# Eight_bit_v1.net
KiCad netlist of a schematic drawn in Altium Designer
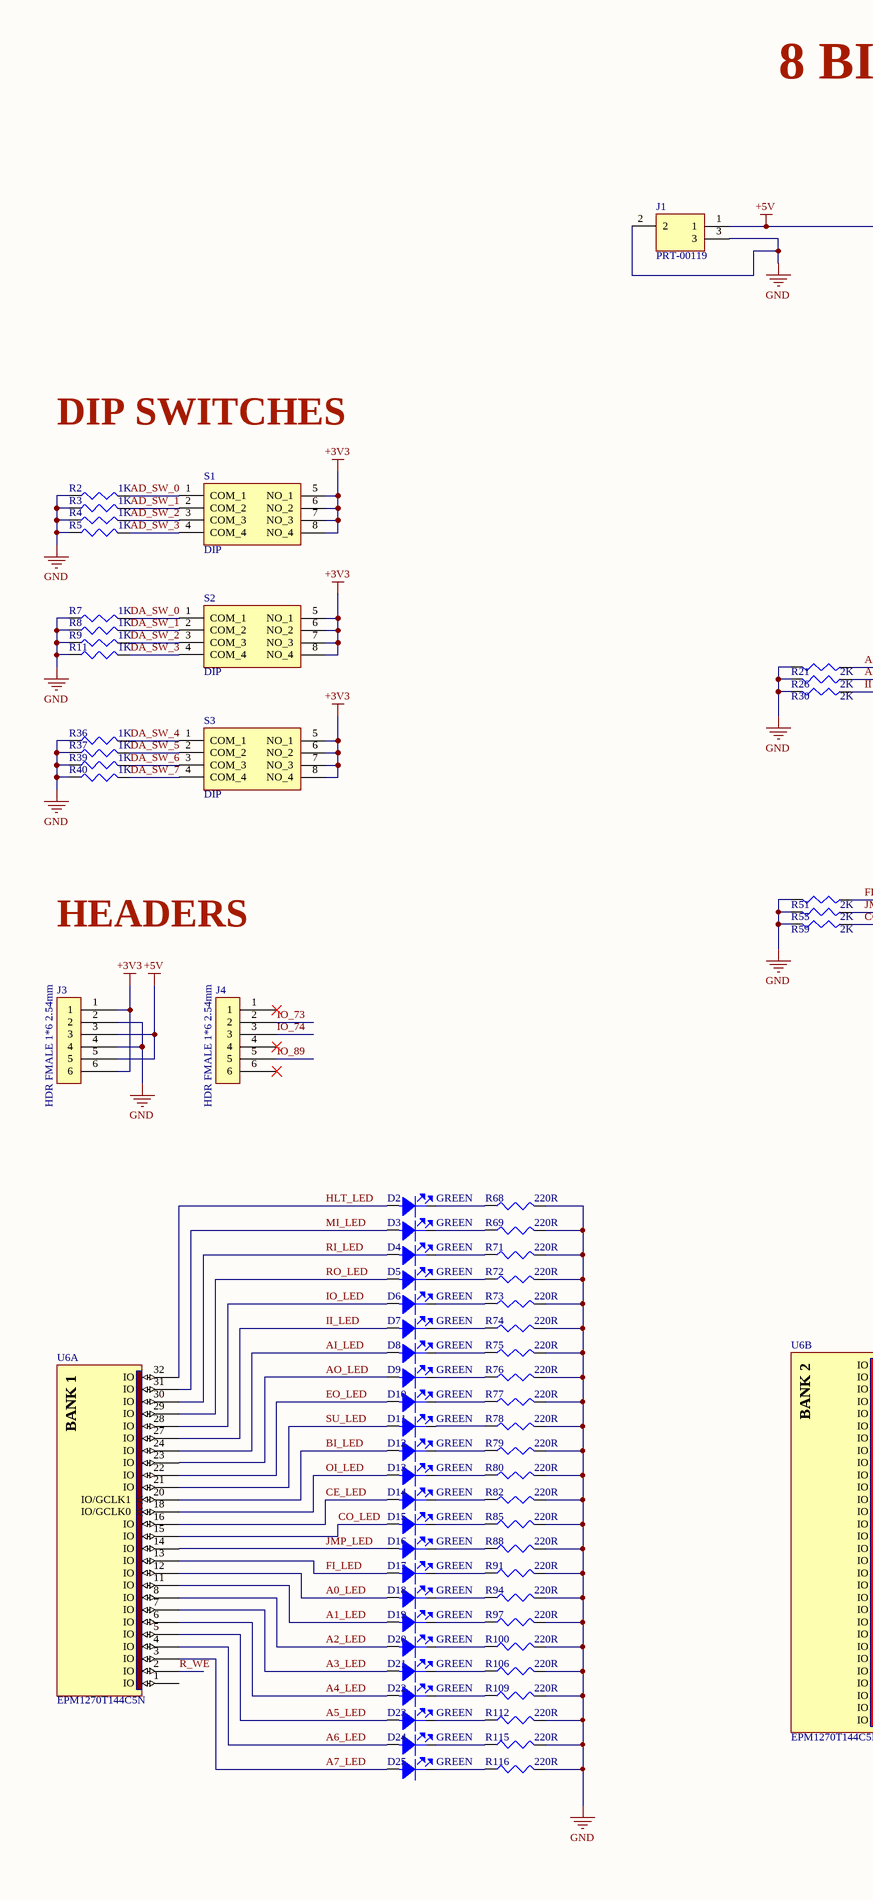
[diagram p0: Eight_bit_v1.SchDoc, left]
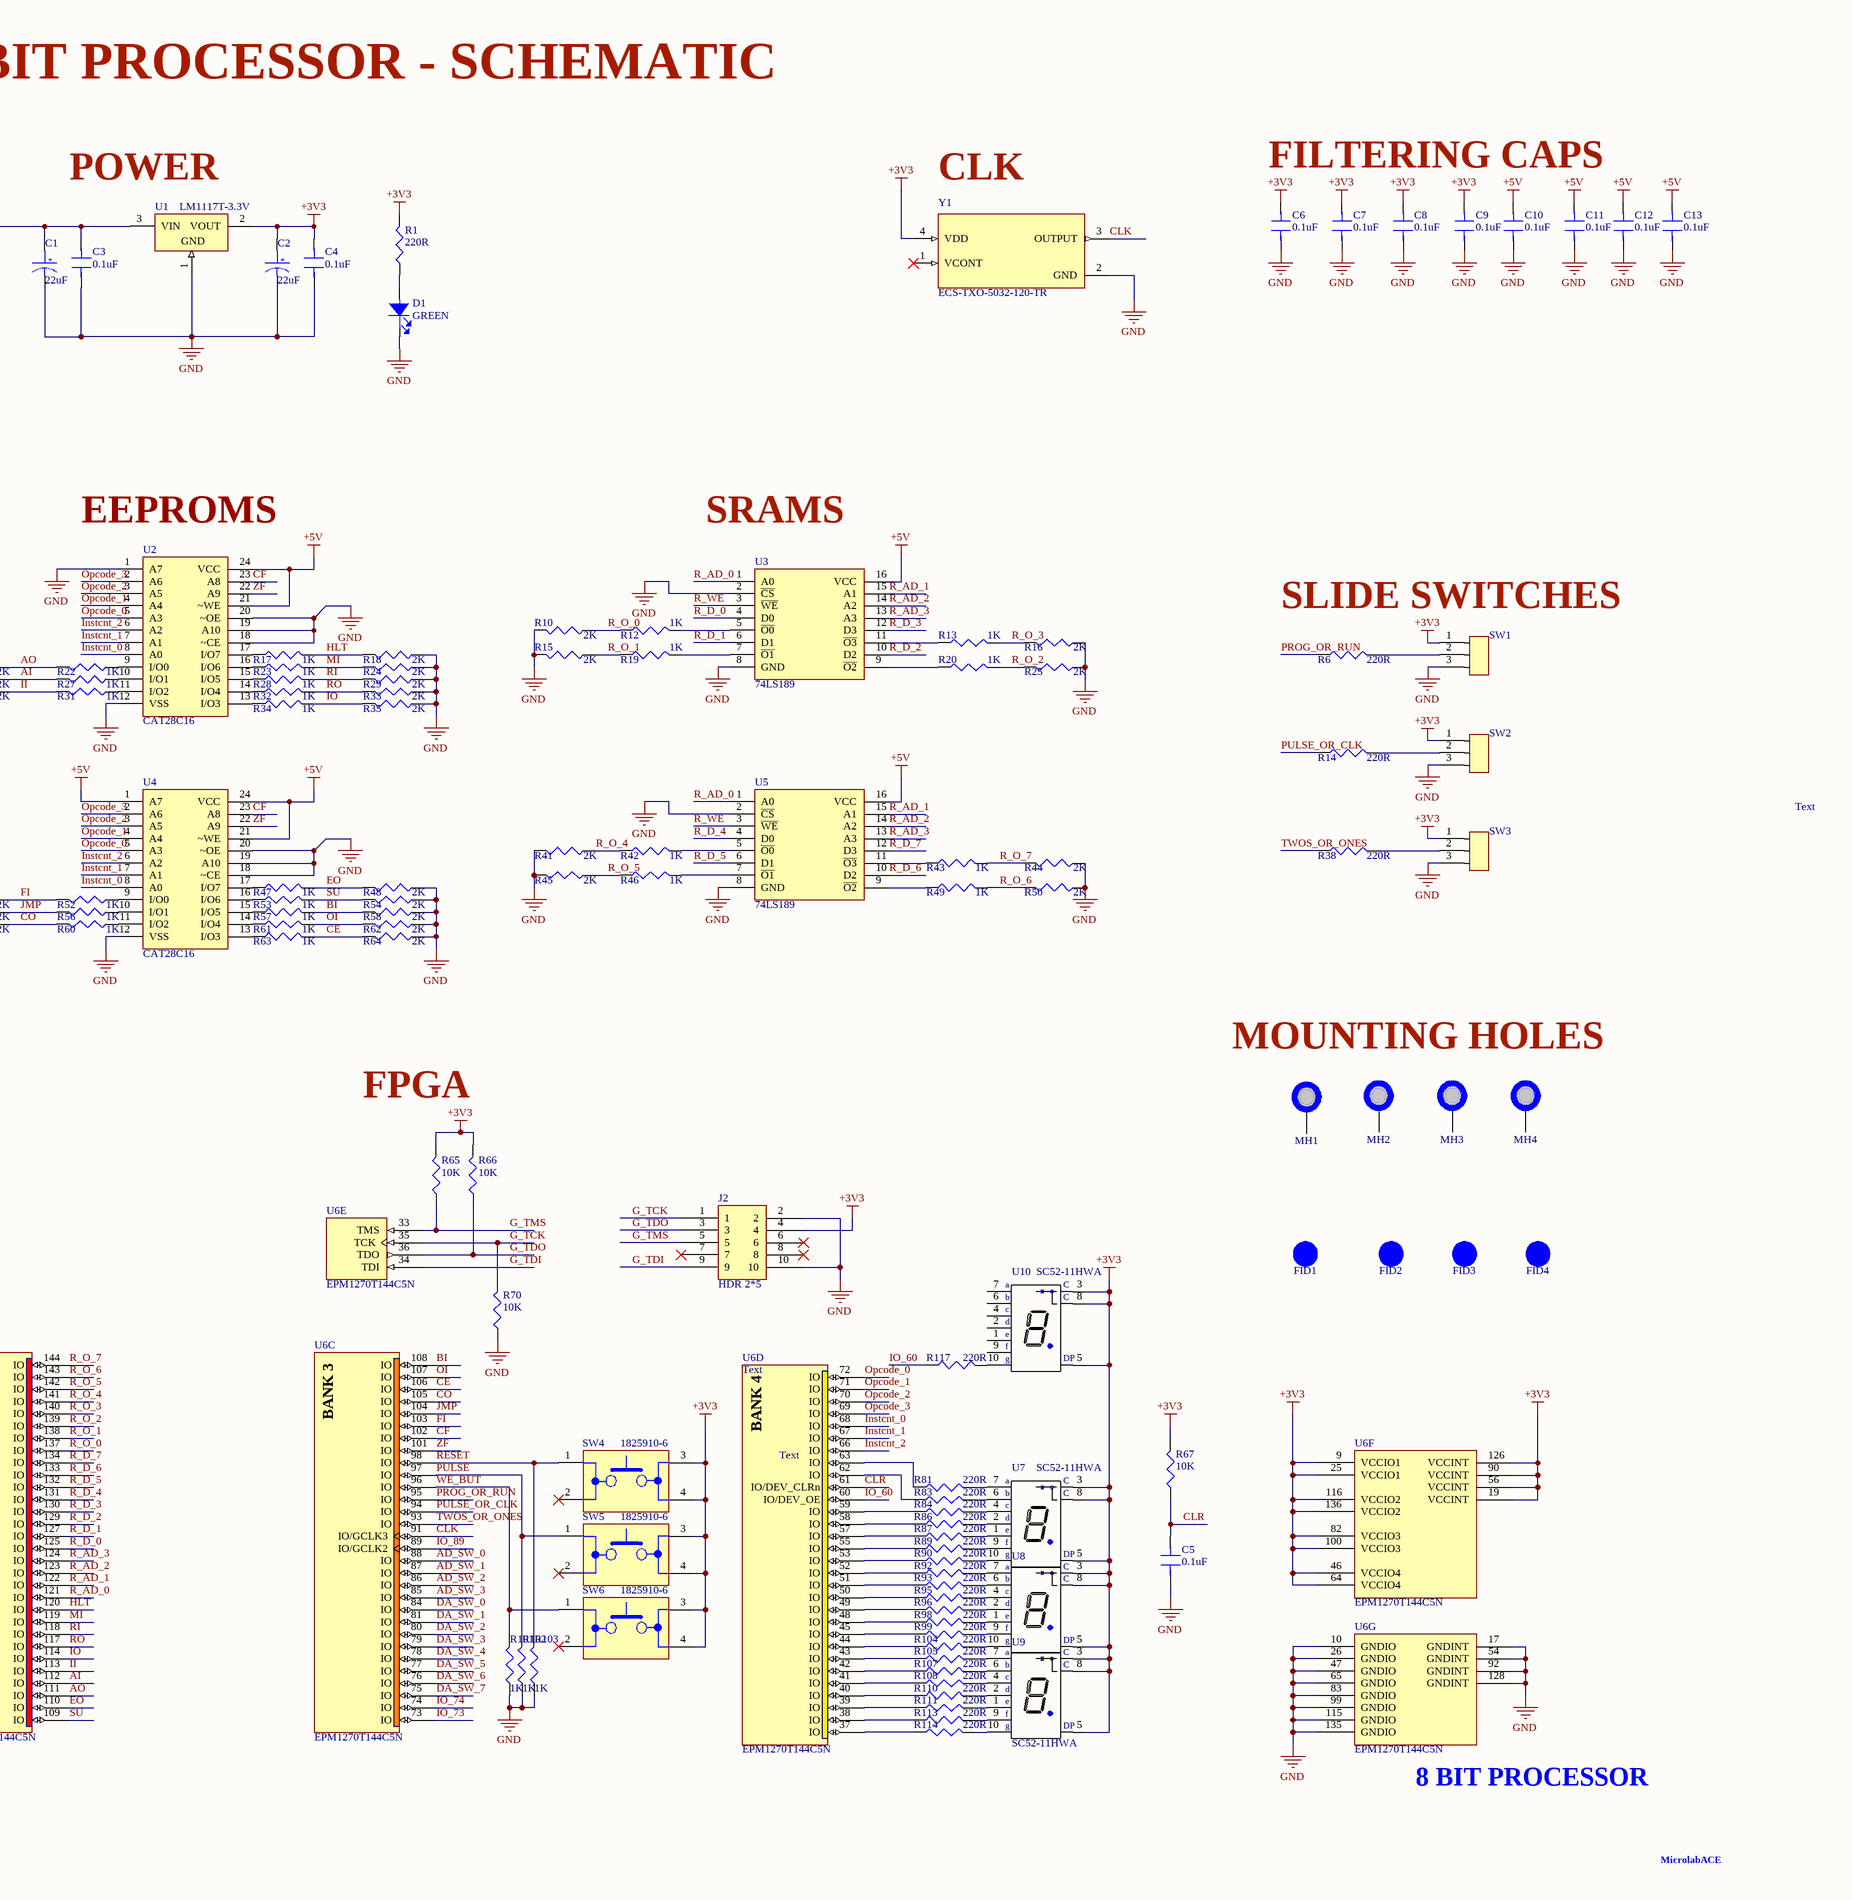
[diagram p1: Eight_bit_v1.SchDoc, right]

(export (version "E")
  (design (tool "Eeschema 10.0.6"))
  (components
    (comp (ref "C1")
      (value "22uF")
      (footprint "CAPPRD200W50D550H1250")
      (description "Cap Aluminum 22uF 25V 20% Radial 2000 hr 85C Ammo Pack")
      (fields
        (field (name "MANUFACTURER") "Panasonic")
        (field (name "MANUFACTURER PART NUMBER") "ECA-1EM220I")
      )
      (libsource (lib "Eight_bit_v1") (part "ECA-1EM220I"))
    )
    (comp (ref "C2")
      (value "22uF")
      (footprint "CAPPRD200W50D550H1250")
      (description "Cap Aluminum 22uF 25V 20% Radial 2000 hr 85C Ammo Pack")
      (fields
        (field (name "MANUFACTURER") "Panasonic")
        (field (name "MANUFACTURER PART NUMBER") "ECA-1EM220I")
      )
      (libsource (lib "Eight_bit_v1") (part "ECA-1EM220I"))
    )
    (comp (ref "C3")
      (value "0.1uF")
      (footprint "C0805")
      (description "Cap Ceramic 0.1uF 50V X7R 10% SMD 2.0 x 1.2 mm 125 C Paper T/R")
      (fields
        (field (name "MANUFACTURER") "KEMET")
        (field (name "MANUFACTURER PART NUMBER") "C0805C104K5RACTU")
      )
      (libsource (lib "Eight_bit_v1") (part "C0805C104K5RACTU"))
    )
    (comp (ref "C4")
      (value "0.1uF")
      (footprint "C0805")
      (description "Cap Ceramic 0.1uF 50V X7R 10% SMD 2.0 x 1.2 mm 125 C Paper T/R")
      (fields
        (field (name "MANUFACTURER") "KEMET")
        (field (name "MANUFACTURER PART NUMBER") "C0805C104K5RACTU")
      )
      (libsource (lib "Eight_bit_v1") (part "C0805C104K5RACTU"))
    )
    (comp (ref "C5")
      (value "0.1uF")
      (footprint "C0805")
      (description "Cap Ceramic 0.1uF 50V X7R 10% SMD 2.0 x 1.2 mm 125 C Paper T/R")
      (fields
        (field (name "MANUFACTURER") "KEMET")
        (field (name "MANUFACTURER PART NUMBER") "C0805C104K5RACTU")
      )
      (libsource (lib "Eight_bit_v1") (part "C0805C104K5RACTU"))
    )
    (comp (ref "C6")
      (value "0.1uF")
      (footprint "C0805")
      (description "Cap Ceramic 0.1uF 50V X7R 10% SMD 2.0 x 1.2 mm 125 C Paper T/R")
      (fields
        (field (name "MANUFACTURER") "KEMET")
        (field (name "MANUFACTURER PART NUMBER") "C0805C104K5RACTU")
      )
      (libsource (lib "Eight_bit_v1") (part "C0805C104K5RACTU"))
    )
    (comp (ref "C7")
      (value "0.1uF")
      (footprint "C0805")
      (description "Cap Ceramic 0.1uF 50V X7R 10% SMD 2.0 x 1.2 mm 125 C Paper T/R")
      (fields
        (field (name "MANUFACTURER") "KEMET")
        (field (name "MANUFACTURER PART NUMBER") "C0805C104K5RACTU")
      )
      (libsource (lib "Eight_bit_v1") (part "C0805C104K5RACTU"))
    )
    (comp (ref "C8")
      (value "0.1uF")
      (footprint "C0805")
      (description "Cap Ceramic 0.1uF 50V X7R 10% SMD 2.0 x 1.2 mm 125 C Paper T/R")
      (fields
        (field (name "MANUFACTURER") "KEMET")
        (field (name "MANUFACTURER PART NUMBER") "C0805C104K5RACTU")
      )
      (libsource (lib "Eight_bit_v1") (part "C0805C104K5RACTU"))
    )
    (comp (ref "C9")
      (value "0.1uF")
      (footprint "C0805")
      (description "Cap Ceramic 0.1uF 50V X7R 10% SMD 2.0 x 1.2 mm 125 C Paper T/R")
      (fields
        (field (name "MANUFACTURER") "KEMET")
        (field (name "MANUFACTURER PART NUMBER") "C0805C104K5RACTU")
      )
      (libsource (lib "Eight_bit_v1") (part "C0805C104K5RACTU"))
    )
    (comp (ref "C10")
      (value "0.1uF")
      (footprint "C0805")
      (description "Cap Ceramic 0.1uF 50V X7R 10% SMD 2.0 x 1.2 mm 125 C Paper T/R")
      (fields
        (field (name "MANUFACTURER") "KEMET")
        (field (name "MANUFACTURER PART NUMBER") "C0805C104K5RACTU")
      )
      (libsource (lib "Eight_bit_v1") (part "C0805C104K5RACTU"))
    )
    (comp (ref "C11")
      (value "0.1uF")
      (footprint "C0805")
      (description "Cap Ceramic 0.1uF 50V X7R 10% SMD 2.0 x 1.2 mm 125 C Paper T/R")
      (fields
        (field (name "MANUFACTURER") "KEMET")
        (field (name "MANUFACTURER PART NUMBER") "C0805C104K5RACTU")
      )
      (libsource (lib "Eight_bit_v1") (part "C0805C104K5RACTU"))
    )
    (comp (ref "C12")
      (value "0.1uF")
      (footprint "C0805")
      (description "Cap Ceramic 0.1uF 50V X7R 10% SMD 2.0 x 1.2 mm 125 C Paper T/R")
      (fields
        (field (name "MANUFACTURER") "KEMET")
        (field (name "MANUFACTURER PART NUMBER") "C0805C104K5RACTU")
      )
      (libsource (lib "Eight_bit_v1") (part "C0805C104K5RACTU"))
    )
    (comp (ref "C13")
      (value "0.1uF")
      (footprint "C0805")
      (description "Cap Ceramic 0.1uF 50V X7R 10% SMD 2.0 x 1.2 mm 125 C Paper T/R")
      (fields
        (field (name "MANUFACTURER") "KEMET")
        (field (name "MANUFACTURER PART NUMBER") "C0805C104K5RACTU")
      )
      (libsource (lib "Eight_bit_v1") (part "C0805C104K5RACTU"))
    )
    (comp (ref "D1")
      (value "GREEN")
      (footprint "LED_0805")
      (description "LED Uni-Color Green 572nm 2-Pin SMD T/R")
      (fields
        (field (name "MANUFACTURER") "Osram Opto")
        (field (name "MANUFACTURER PART NUMBER") "LGR971-KN-1")
      )
      (libsource (lib "Eight_bit_v1") (part "LGR971-KN-1"))
    )
    (comp (ref "D2")
      (value "GREEN")
      (footprint "LED_0805")
      (description "LED Uni-Color Green 572nm 2-Pin SMD T/R")
      (fields
        (field (name "MANUFACTURER") "Osram Opto")
        (field (name "MANUFACTURER PART NUMBER") "LGR971-KN-1")
      )
      (libsource (lib "Eight_bit_v1") (part "LGR971-KN-1"))
    )
    (comp (ref "D3")
      (value "GREEN")
      (footprint "LED_0805")
      (description "LED Uni-Color Green 572nm 2-Pin SMD T/R")
      (fields
        (field (name "MANUFACTURER") "Osram Opto")
        (field (name "MANUFACTURER PART NUMBER") "LGR971-KN-1")
      )
      (libsource (lib "Eight_bit_v1") (part "LGR971-KN-1"))
    )
    (comp (ref "D4")
      (value "GREEN")
      (footprint "LED_0805")
      (description "LED Uni-Color Green 572nm 2-Pin SMD T/R")
      (fields
        (field (name "MANUFACTURER") "Osram Opto")
        (field (name "MANUFACTURER PART NUMBER") "LGR971-KN-1")
      )
      (libsource (lib "Eight_bit_v1") (part "LGR971-KN-1"))
    )
    (comp (ref "D5")
      (value "GREEN")
      (footprint "LED_0805")
      (description "LED Uni-Color Green 572nm 2-Pin SMD T/R")
      (fields
        (field (name "MANUFACTURER") "Osram Opto")
        (field (name "MANUFACTURER PART NUMBER") "LGR971-KN-1")
      )
      (libsource (lib "Eight_bit_v1") (part "LGR971-KN-1"))
    )
    (comp (ref "D6")
      (value "GREEN")
      (footprint "LED_0805")
      (description "LED Uni-Color Green 572nm 2-Pin SMD T/R")
      (fields
        (field (name "MANUFACTURER") "Osram Opto")
        (field (name "MANUFACTURER PART NUMBER") "LGR971-KN-1")
      )
      (libsource (lib "Eight_bit_v1") (part "LGR971-KN-1"))
    )
    (comp (ref "D7")
      (value "GREEN")
      (footprint "LED_0805")
      (description "LED Uni-Color Green 572nm 2-Pin SMD T/R")
      (fields
        (field (name "MANUFACTURER") "Osram Opto")
        (field (name "MANUFACTURER PART NUMBER") "LGR971-KN-1")
      )
      (libsource (lib "Eight_bit_v1") (part "LGR971-KN-1"))
    )
    (comp (ref "D8")
      (value "GREEN")
      (footprint "LED_0805")
      (description "LED Uni-Color Green 572nm 2-Pin SMD T/R")
      (fields
        (field (name "MANUFACTURER") "Osram Opto")
        (field (name "MANUFACTURER PART NUMBER") "LGR971-KN-1")
      )
      (libsource (lib "Eight_bit_v1") (part "LGR971-KN-1"))
    )
    (comp (ref "D9")
      (value "GREEN")
      (footprint "LED_0805")
      (description "LED Uni-Color Green 572nm 2-Pin SMD T/R")
      (fields
        (field (name "MANUFACTURER") "Osram Opto")
        (field (name "MANUFACTURER PART NUMBER") "LGR971-KN-1")
      )
      (libsource (lib "Eight_bit_v1") (part "LGR971-KN-1"))
    )
    (comp (ref "D10")
      (value "GREEN")
      (footprint "LED_0805")
      (description "LED Uni-Color Green 572nm 2-Pin SMD T/R")
      (fields
        (field (name "MANUFACTURER") "Osram Opto")
        (field (name "MANUFACTURER PART NUMBER") "LGR971-KN-1")
      )
      (libsource (lib "Eight_bit_v1") (part "LGR971-KN-1"))
    )
    (comp (ref "D11")
      (value "GREEN")
      (footprint "LED_0805")
      (description "LED Uni-Color Green 572nm 2-Pin SMD T/R")
      (fields
        (field (name "MANUFACTURER") "Osram Opto")
        (field (name "MANUFACTURER PART NUMBER") "LGR971-KN-1")
      )
      (libsource (lib "Eight_bit_v1") (part "LGR971-KN-1"))
    )
    (comp (ref "D12")
      (value "GREEN")
      (footprint "LED_0805")
      (description "LED Uni-Color Green 572nm 2-Pin SMD T/R")
      (fields
        (field (name "MANUFACTURER") "Osram Opto")
        (field (name "MANUFACTURER PART NUMBER") "LGR971-KN-1")
      )
      (libsource (lib "Eight_bit_v1") (part "LGR971-KN-1"))
    )
    (comp (ref "D13")
      (value "GREEN")
      (footprint "LED_0805")
      (description "LED Uni-Color Green 572nm 2-Pin SMD T/R")
      (fields
        (field (name "MANUFACTURER") "Osram Opto")
        (field (name "MANUFACTURER PART NUMBER") "LGR971-KN-1")
      )
      (libsource (lib "Eight_bit_v1") (part "LGR971-KN-1"))
    )
    (comp (ref "D14")
      (value "GREEN")
      (footprint "LED_0805")
      (description "LED Uni-Color Green 572nm 2-Pin SMD T/R")
      (fields
        (field (name "MANUFACTURER") "Osram Opto")
        (field (name "MANUFACTURER PART NUMBER") "LGR971-KN-1")
      )
      (libsource (lib "Eight_bit_v1") (part "LGR971-KN-1"))
    )
    (comp (ref "D15")
      (value "GREEN")
      (footprint "LED_0805")
      (description "LED Uni-Color Green 572nm 2-Pin SMD T/R")
      (fields
        (field (name "MANUFACTURER") "Osram Opto")
        (field (name "MANUFACTURER PART NUMBER") "LGR971-KN-1")
      )
      (libsource (lib "Eight_bit_v1") (part "LGR971-KN-1"))
    )
    (comp (ref "D16")
      (value "GREEN")
      (footprint "LED_0805")
      (description "LED Uni-Color Green 572nm 2-Pin SMD T/R")
      (fields
        (field (name "MANUFACTURER") "Osram Opto")
        (field (name "MANUFACTURER PART NUMBER") "LGR971-KN-1")
      )
      (libsource (lib "Eight_bit_v1") (part "LGR971-KN-1"))
    )
    (comp (ref "D17")
      (value "GREEN")
      (footprint "LED_0805")
      (description "LED Uni-Color Green 572nm 2-Pin SMD T/R")
      (fields
        (field (name "MANUFACTURER") "Osram Opto")
        (field (name "MANUFACTURER PART NUMBER") "LGR971-KN-1")
      )
      (libsource (lib "Eight_bit_v1") (part "LGR971-KN-1"))
    )
    (comp (ref "D18")
      (value "GREEN")
      (footprint "LED_0805")
      (description "LED Uni-Color Green 572nm 2-Pin SMD T/R")
      (fields
        (field (name "MANUFACTURER") "Osram Opto")
        (field (name "MANUFACTURER PART NUMBER") "LGR971-KN-1")
      )
      (libsource (lib "Eight_bit_v1") (part "LGR971-KN-1"))
    )
    (comp (ref "D19")
      (value "GREEN")
      (footprint "LED_0805")
      (description "LED Uni-Color Green 572nm 2-Pin SMD T/R")
      (fields
        (field (name "MANUFACTURER") "Osram Opto")
        (field (name "MANUFACTURER PART NUMBER") "LGR971-KN-1")
      )
      (libsource (lib "Eight_bit_v1") (part "LGR971-KN-1"))
    )
    (comp (ref "D20")
      (value "GREEN")
      (footprint "LED_0805")
      (description "LED Uni-Color Green 572nm 2-Pin SMD T/R")
      (fields
        (field (name "MANUFACTURER") "Osram Opto")
        (field (name "MANUFACTURER PART NUMBER") "LGR971-KN-1")
      )
      (libsource (lib "Eight_bit_v1") (part "LGR971-KN-1"))
    )
    (comp (ref "D21")
      (value "GREEN")
      (footprint "LED_0805")
      (description "LED Uni-Color Green 572nm 2-Pin SMD T/R")
      (fields
        (field (name "MANUFACTURER") "Osram Opto")
        (field (name "MANUFACTURER PART NUMBER") "LGR971-KN-1")
      )
      (libsource (lib "Eight_bit_v1") (part "LGR971-KN-1"))
    )
    (comp (ref "D22")
      (value "GREEN")
      (footprint "LED_0805")
      (description "LED Uni-Color Green 572nm 2-Pin SMD T/R")
      (fields
        (field (name "MANUFACTURER") "Osram Opto")
        (field (name "MANUFACTURER PART NUMBER") "LGR971-KN-1")
      )
      (libsource (lib "Eight_bit_v1") (part "LGR971-KN-1"))
    )
    (comp (ref "D23")
      (value "GREEN")
      (footprint "LED_0805")
      (description "LED Uni-Color Green 572nm 2-Pin SMD T/R")
      (fields
        (field (name "MANUFACTURER") "Osram Opto")
        (field (name "MANUFACTURER PART NUMBER") "LGR971-KN-1")
      )
      (libsource (lib "Eight_bit_v1") (part "LGR971-KN-1"))
    )
    (comp (ref "D24")
      (value "GREEN")
      (footprint "LED_0805")
      (description "LED Uni-Color Green 572nm 2-Pin SMD T/R")
      (fields
        (field (name "MANUFACTURER") "Osram Opto")
        (field (name "MANUFACTURER PART NUMBER") "LGR971-KN-1")
      )
      (libsource (lib "Eight_bit_v1") (part "LGR971-KN-1"))
    )
    (comp (ref "D25")
      (value "GREEN")
      (footprint "LED_0805")
      (description "LED Uni-Color Green 572nm 2-Pin SMD T/R")
      (fields
        (field (name "MANUFACTURER") "Osram Opto")
        (field (name "MANUFACTURER PART NUMBER") "LGR971-KN-1")
      )
      (libsource (lib "Eight_bit_v1") (part "LGR971-KN-1"))
    )
    (comp (ref "FID1")
      (value "FID_1MMC")
      (footprint "FID_40x120D")
      (description "Fiducial 40mil Diameter 120mil Mask")
      (libsource (lib "Eight_bit_v1") (part "FID_1MMC"))
    )
    (comp (ref "FID2")
      (value "FID_1MMC")
      (footprint "FID_40x120D")
      (description "Fiducial 40mil Diameter 120mil Mask")
      (libsource (lib "Eight_bit_v1") (part "FID_1MMC"))
    )
    (comp (ref "FID3")
      (value "FID_1MMC")
      (footprint "FID_40x120D")
      (description "Fiducial 40mil Diameter 120mil Mask")
      (libsource (lib "Eight_bit_v1") (part "FID_1MMC"))
    )
    (comp (ref "FID4")
      (value "FID_1MMC")
      (footprint "FID_40x120D")
      (description "Fiducial 40mil Diameter 120mil Mask")
      (libsource (lib "Eight_bit_v1") (part "FID_1MMC"))
    )
    (comp (ref "J1")
      (value "PRT-00119")
      (footprint "SamacSys:PRT00119")
      (description "Connector")
      (fields (field (name "MOUSER PART NUMBER") "474-PRT-00119"))
      (libsource (lib "Eight_bit_v1") (part "PRT-00119"))
    )
    (comp (ref "J2")
      (value "HDR 2*5")
      (footprint "HDR_2X5_2.54MM")
      (description "CONN HEADER 10POS .100 STR 30AU")
      (fields
        (field (name "MANUFACTURER") "Amphenol FCI")
        (field (name "MANUFACTURER PART NUMBER") "67997-110HLF")
      )
      (libsource (lib "Eight_bit_v1") (part "67997-110HLF"))
    )
    (comp (ref "J3")
      (value "HDR FMALE 1*6 2.54mm")
      (footprint "Hdr_Female_1*6_2.54mm")
      (description "06-WAY SIL VERT SOCKET L/FREE")
      (fields (field (name "MANUFACTURER") "Harwin") (field (name "MANUFACTURER PART NUMBER") "M20-7820646"))
      (libsource (lib "Eight_bit_v1") (part "M20-7820646"))
    )
    (comp (ref "J4")
      (value "HDR FMALE 1*6 2.54mm")
      (footprint "Hdr_Female_1*6_2.54mm")
      (description "06-WAY SIL VERT SOCKET L/FREE")
      (fields (field (name "MANUFACTURER") "Harwin") (field (name "MANUFACTURER PART NUMBER") "M20-7820646"))
      (libsource (lib "Eight_bit_v1") (part "M20-7820646"))
    )
    (comp (ref "MH1")
      (value "MH_7.4MMNC_3.2MMD")
      (footprint "MH_7.4MMND_3.2MMD_NON_COPPER_NPTH")
      (description "Mounting Hole 7.4mm Diameter (Non Copper), 3.2mm Drill NPTH")
      (libsource (lib "Eight_bit_v1") (part "MH_7.4MMNC_3.2MMD"))
    )
    (comp (ref "MH2")
      (value "MH_7.4MMNC_3.2MMD")
      (footprint "MH_7.4MMND_3.2MMD_NON_COPPER_NPTH")
      (description "Mounting Hole 7.4mm Diameter (Non Copper), 3.2mm Drill NPTH")
      (libsource (lib "Eight_bit_v1") (part "MH_7.4MMNC_3.2MMD"))
    )
    (comp (ref "MH3")
      (value "MH_7.4MMNC_3.2MMD")
      (footprint "MH_7.4MMND_3.2MMD_NON_COPPER_NPTH")
      (description "Mounting Hole 7.4mm Diameter (Non Copper), 3.2mm Drill NPTH")
      (libsource (lib "Eight_bit_v1") (part "MH_7.4MMNC_3.2MMD"))
    )
    (comp (ref "MH4")
      (value "MH_7.4MMNC_3.2MMD")
      (footprint "MH_7.4MMND_3.2MMD_NON_COPPER_NPTH")
      (description "Mounting Hole 7.4mm Diameter (Non Copper), 3.2mm Drill NPTH")
      (libsource (lib "Eight_bit_v1") (part "MH_7.4MMNC_3.2MMD"))
    )
    (comp (ref "R1")
      (value "220R")
      (footprint "R0805")
      (description "RES SMD 220 OHM 1% 1/8W 0805")
      (fields
        (field (name "MANUFACTURER") "Yageo")
        (field (name "MANUFACTURER PART NUMBER") "RC0805FR-07220RL")
      )
      (libsource (lib "Eight_bit_v1") (part "RC0805FR-07220RL"))
    )
    (comp (ref "R2")
      (value "1K")
      (footprint "R0805")
      (description "RES SMD 1K OHM 1% 1/8W 0805")
      (fields
        (field (name "MANUFACTURER") "Yageo Phycomp")
        (field (name "MANUFACTURER PART NUMBER") "RC0805FR-071KL")
      )
      (libsource (lib "Eight_bit_v1") (part "RC0805FR-071KL"))
    )
    (comp (ref "R3")
      (value "1K")
      (footprint "R0805")
      (description "RES SMD 1K OHM 1% 1/8W 0805")
      (fields
        (field (name "MANUFACTURER") "Yageo Phycomp")
        (field (name "MANUFACTURER PART NUMBER") "RC0805FR-071KL")
      )
      (libsource (lib "Eight_bit_v1") (part "RC0805FR-071KL"))
    )
    (comp (ref "R4")
      (value "1K")
      (footprint "R0805")
      (description "RES SMD 1K OHM 1% 1/8W 0805")
      (fields
        (field (name "MANUFACTURER") "Yageo Phycomp")
        (field (name "MANUFACTURER PART NUMBER") "RC0805FR-071KL")
      )
      (libsource (lib "Eight_bit_v1") (part "RC0805FR-071KL"))
    )
    (comp (ref "R5")
      (value "1K")
      (footprint "R0805")
      (description "RES SMD 1K OHM 1% 1/8W 0805")
      (fields
        (field (name "MANUFACTURER") "Yageo Phycomp")
        (field (name "MANUFACTURER PART NUMBER") "RC0805FR-071KL")
      )
      (libsource (lib "Eight_bit_v1") (part "RC0805FR-071KL"))
    )
    (comp (ref "R6")
      (value "220R")
      (footprint "R0805")
      (description "RES SMD 220 OHM 1% 1/8W 0805")
      (fields
        (field (name "MANUFACTURER") "Yageo")
        (field (name "MANUFACTURER PART NUMBER") "RC0805FR-07220RL")
      )
      (libsource (lib "Eight_bit_v1") (part "RC0805FR-07220RL"))
    )
    (comp (ref "R7")
      (value "1K")
      (footprint "R0805")
      (description "RES SMD 1K OHM 1% 1/8W 0805")
      (fields
        (field (name "MANUFACTURER") "Yageo Phycomp")
        (field (name "MANUFACTURER PART NUMBER") "RC0805FR-071KL")
      )
      (libsource (lib "Eight_bit_v1") (part "RC0805FR-071KL"))
    )
    (comp (ref "R8")
      (value "1K")
      (footprint "R0805")
      (description "RES SMD 1K OHM 1% 1/8W 0805")
      (fields
        (field (name "MANUFACTURER") "Yageo Phycomp")
        (field (name "MANUFACTURER PART NUMBER") "RC0805FR-071KL")
      )
      (libsource (lib "Eight_bit_v1") (part "RC0805FR-071KL"))
    )
    (comp (ref "R9")
      (value "1K")
      (footprint "R0805")
      (description "RES SMD 1K OHM 1% 1/8W 0805")
      (fields
        (field (name "MANUFACTURER") "Yageo Phycomp")
        (field (name "MANUFACTURER PART NUMBER") "RC0805FR-071KL")
      )
      (libsource (lib "Eight_bit_v1") (part "RC0805FR-071KL"))
    )
    (comp (ref "R10")
      (value "2K")
      (footprint "R0805")
      (description "RES SMD 2K OHM 1% 1/8W 0805")
      (fields
        (field (name "MANUFACTURER") "Yageo")
        (field (name "MANUFACTURER PART NUMBER") "RC0805FR-072KL")
      )
      (libsource (lib "Eight_bit_v1") (part "RC0805FR-072KL"))
    )
    (comp (ref "R11")
      (value "1K")
      (footprint "R0805")
      (description "RES SMD 1K OHM 1% 1/8W 0805")
      (fields
        (field (name "MANUFACTURER") "Yageo Phycomp")
        (field (name "MANUFACTURER PART NUMBER") "RC0805FR-071KL")
      )
      (libsource (lib "Eight_bit_v1") (part "RC0805FR-071KL"))
    )
    (comp (ref "R12")
      (value "1K")
      (footprint "R0805")
      (description "RES SMD 1K OHM 1% 1/8W 0805")
      (fields
        (field (name "MANUFACTURER") "Yageo Phycomp")
        (field (name "MANUFACTURER PART NUMBER") "RC0805FR-071KL")
      )
      (libsource (lib "Eight_bit_v1") (part "RC0805FR-071KL"))
    )
    (comp (ref "R13")
      (value "1K")
      (footprint "R0805")
      (description "RES SMD 1K OHM 1% 1/8W 0805")
      (fields
        (field (name "MANUFACTURER") "Yageo Phycomp")
        (field (name "MANUFACTURER PART NUMBER") "RC0805FR-071KL")
      )
      (libsource (lib "Eight_bit_v1") (part "RC0805FR-071KL"))
    )
    (comp (ref "R14")
      (value "220R")
      (footprint "R0805")
      (description "RES SMD 220 OHM 1% 1/8W 0805")
      (fields
        (field (name "MANUFACTURER") "Yageo")
        (field (name "MANUFACTURER PART NUMBER") "RC0805FR-07220RL")
      )
      (libsource (lib "Eight_bit_v1") (part "RC0805FR-07220RL"))
    )
    (comp (ref "R15")
      (value "2K")
      (footprint "R0805")
      (description "RES SMD 2K OHM 1% 1/8W 0805")
      (fields
        (field (name "MANUFACTURER") "Yageo")
        (field (name "MANUFACTURER PART NUMBER") "RC0805FR-072KL")
      )
      (libsource (lib "Eight_bit_v1") (part "RC0805FR-072KL"))
    )
    (comp (ref "R16")
      (value "2K")
      (footprint "R0805")
      (description "RES SMD 2K OHM 1% 1/8W 0805")
      (fields
        (field (name "MANUFACTURER") "Yageo")
        (field (name "MANUFACTURER PART NUMBER") "RC0805FR-072KL")
      )
      (libsource (lib "Eight_bit_v1") (part "RC0805FR-072KL"))
    )
    (comp (ref "R17")
      (value "1K")
      (footprint "R0805")
      (description "RES SMD 1K OHM 1% 1/8W 0805")
      (fields
        (field (name "MANUFACTURER") "Yageo Phycomp")
        (field (name "MANUFACTURER PART NUMBER") "RC0805FR-071KL")
      )
      (libsource (lib "Eight_bit_v1") (part "RC0805FR-071KL"))
    )
    (comp (ref "R18")
      (value "2K")
      (footprint "R0805")
      (description "RES SMD 2K OHM 1% 1/8W 0805")
      (fields
        (field (name "MANUFACTURER") "Yageo")
        (field (name "MANUFACTURER PART NUMBER") "RC0805FR-072KL")
      )
      (libsource (lib "Eight_bit_v1") (part "RC0805FR-072KL"))
    )
    (comp (ref "R19")
      (value "1K")
      (footprint "R0805")
      (description "RES SMD 1K OHM 1% 1/8W 0805")
      (fields
        (field (name "MANUFACTURER") "Yageo Phycomp")
        (field (name "MANUFACTURER PART NUMBER") "RC0805FR-071KL")
      )
      (libsource (lib "Eight_bit_v1") (part "RC0805FR-071KL"))
    )
    (comp (ref "R20")
      (value "1K")
      (footprint "R0805")
      (description "RES SMD 1K OHM 1% 1/8W 0805")
      (fields
        (field (name "MANUFACTURER") "Yageo Phycomp")
        (field (name "MANUFACTURER PART NUMBER") "RC0805FR-071KL")
      )
      (libsource (lib "Eight_bit_v1") (part "RC0805FR-071KL"))
    )
    (comp (ref "R21")
      (value "2K")
      (footprint "R0805")
      (description "RES SMD 2K OHM 1% 1/8W 0805")
      (fields
        (field (name "MANUFACTURER") "Yageo")
        (field (name "MANUFACTURER PART NUMBER") "RC0805FR-072KL")
      )
      (libsource (lib "Eight_bit_v1") (part "RC0805FR-072KL"))
    )
    (comp (ref "R22")
      (value "1K")
      (footprint "R0805")
      (description "RES SMD 1K OHM 1% 1/8W 0805")
      (fields
        (field (name "MANUFACTURER") "Yageo Phycomp")
        (field (name "MANUFACTURER PART NUMBER") "RC0805FR-071KL")
      )
      (libsource (lib "Eight_bit_v1") (part "RC0805FR-071KL"))
    )
    (comp (ref "R23")
      (value "1K")
      (footprint "R0805")
      (description "RES SMD 1K OHM 1% 1/8W 0805")
      (fields
        (field (name "MANUFACTURER") "Yageo Phycomp")
        (field (name "MANUFACTURER PART NUMBER") "RC0805FR-071KL")
      )
      (libsource (lib "Eight_bit_v1") (part "RC0805FR-071KL"))
    )
    (comp (ref "R24")
      (value "2K")
      (footprint "R0805")
      (description "RES SMD 2K OHM 1% 1/8W 0805")
      (fields
        (field (name "MANUFACTURER") "Yageo")
        (field (name "MANUFACTURER PART NUMBER") "RC0805FR-072KL")
      )
      (libsource (lib "Eight_bit_v1") (part "RC0805FR-072KL"))
    )
    (comp (ref "R25")
      (value "2K")
      (footprint "R0805")
      (description "RES SMD 2K OHM 1% 1/8W 0805")
      (fields
        (field (name "MANUFACTURER") "Yageo")
        (field (name "MANUFACTURER PART NUMBER") "RC0805FR-072KL")
      )
      (libsource (lib "Eight_bit_v1") (part "RC0805FR-072KL"))
    )
    (comp (ref "R26")
      (value "2K")
      (footprint "R0805")
      (description "RES SMD 2K OHM 1% 1/8W 0805")
      (fields
        (field (name "MANUFACTURER") "Yageo")
        (field (name "MANUFACTURER PART NUMBER") "RC0805FR-072KL")
      )
      (libsource (lib "Eight_bit_v1") (part "RC0805FR-072KL"))
    )
    (comp (ref "R27")
      (value "1K")
      (footprint "R0805")
      (description "RES SMD 1K OHM 1% 1/8W 0805")
      (fields
        (field (name "MANUFACTURER") "Yageo Phycomp")
        (field (name "MANUFACTURER PART NUMBER") "RC0805FR-071KL")
      )
      (libsource (lib "Eight_bit_v1") (part "RC0805FR-071KL"))
    )
    (comp (ref "R28")
      (value "1K")
      (footprint "R0805")
      (description "RES SMD 1K OHM 1% 1/8W 0805")
      (fields
        (field (name "MANUFACTURER") "Yageo Phycomp")
        (field (name "MANUFACTURER PART NUMBER") "RC0805FR-071KL")
      )
      (libsource (lib "Eight_bit_v1") (part "RC0805FR-071KL"))
    )
    (comp (ref "R29")
      (value "2K")
      (footprint "R0805")
      (description "RES SMD 2K OHM 1% 1/8W 0805")
      (fields
        (field (name "MANUFACTURER") "Yageo")
        (field (name "MANUFACTURER PART NUMBER") "RC0805FR-072KL")
      )
      (libsource (lib "Eight_bit_v1") (part "RC0805FR-072KL"))
    )
    (comp (ref "R30")
      (value "2K")
      (footprint "R0805")
      (description "RES SMD 2K OHM 1% 1/8W 0805")
      (fields
        (field (name "MANUFACTURER") "Yageo")
        (field (name "MANUFACTURER PART NUMBER") "RC0805FR-072KL")
      )
      (libsource (lib "Eight_bit_v1") (part "RC0805FR-072KL"))
    )
    (comp (ref "R31")
      (value "1K")
      (footprint "R0805")
      (description "RES SMD 1K OHM 1% 1/8W 0805")
      (fields
        (field (name "MANUFACTURER") "Yageo Phycomp")
        (field (name "MANUFACTURER PART NUMBER") "RC0805FR-071KL")
      )
      (libsource (lib "Eight_bit_v1") (part "RC0805FR-071KL"))
    )
    (comp (ref "R32")
      (value "1K")
      (footprint "R0805")
      (description "RES SMD 1K OHM 1% 1/8W 0805")
      (fields
        (field (name "MANUFACTURER") "Yageo Phycomp")
        (field (name "MANUFACTURER PART NUMBER") "RC0805FR-071KL")
      )
      (libsource (lib "Eight_bit_v1") (part "RC0805FR-071KL"))
    )
    (comp (ref "R33")
      (value "2K")
      (footprint "R0805")
      (description "RES SMD 2K OHM 1% 1/8W 0805")
      (fields
        (field (name "MANUFACTURER") "Yageo")
        (field (name "MANUFACTURER PART NUMBER") "RC0805FR-072KL")
      )
      (libsource (lib "Eight_bit_v1") (part "RC0805FR-072KL"))
    )
    (comp (ref "R34")
      (value "1K")
      (footprint "R0805")
      (description "RES SMD 1K OHM 1% 1/8W 0805")
      (fields
        (field (name "MANUFACTURER") "Yageo Phycomp")
        (field (name "MANUFACTURER PART NUMBER") "RC0805FR-071KL")
      )
      (libsource (lib "Eight_bit_v1") (part "RC0805FR-071KL"))
    )
    (comp (ref "R35")
      (value "2K")
      (footprint "R0805")
      (description "RES SMD 2K OHM 1% 1/8W 0805")
      (fields
        (field (name "MANUFACTURER") "Yageo")
        (field (name "MANUFACTURER PART NUMBER") "RC0805FR-072KL")
      )
      (libsource (lib "Eight_bit_v1") (part "RC0805FR-072KL"))
    )
    (comp (ref "R36")
      (value "1K")
      (footprint "R0805")
      (description "RES SMD 1K OHM 1% 1/8W 0805")
      (fields
        (field (name "MANUFACTURER") "Yageo Phycomp")
        (field (name "MANUFACTURER PART NUMBER") "RC0805FR-071KL")
      )
      (libsource (lib "Eight_bit_v1") (part "RC0805FR-071KL"))
    )
    (comp (ref "R37")
      (value "1K")
      (footprint "R0805")
      (description "RES SMD 1K OHM 1% 1/8W 0805")
      (fields
        (field (name "MANUFACTURER") "Yageo Phycomp")
        (field (name "MANUFACTURER PART NUMBER") "RC0805FR-071KL")
      )
      (libsource (lib "Eight_bit_v1") (part "RC0805FR-071KL"))
    )
    (comp (ref "R38")
      (value "220R")
      (footprint "R0805")
      (description "RES SMD 220 OHM 1% 1/8W 0805")
      (fields
        (field (name "MANUFACTURER") "Yageo")
        (field (name "MANUFACTURER PART NUMBER") "RC0805FR-07220RL")
      )
      (libsource (lib "Eight_bit_v1") (part "RC0805FR-07220RL"))
    )
    (comp (ref "R39")
      (value "1K")
      (footprint "R0805")
      (description "RES SMD 1K OHM 1% 1/8W 0805")
      (fields
        (field (name "MANUFACTURER") "Yageo Phycomp")
        (field (name "MANUFACTURER PART NUMBER") "RC0805FR-071KL")
      )
      (libsource (lib "Eight_bit_v1") (part "RC0805FR-071KL"))
    )
    (comp (ref "R40")
      (value "1K")
      (footprint "R0805")
      (description "RES SMD 1K OHM 1% 1/8W 0805")
      (fields
        (field (name "MANUFACTURER") "Yageo Phycomp")
        (field (name "MANUFACTURER PART NUMBER") "RC0805FR-071KL")
      )
      (libsource (lib "Eight_bit_v1") (part "RC0805FR-071KL"))
    )
    (comp (ref "R41")
      (value "2K")
      (footprint "R0805")
      (description "RES SMD 2K OHM 1% 1/8W 0805")
      (fields
        (field (name "MANUFACTURER") "Yageo")
        (field (name "MANUFACTURER PART NUMBER") "RC0805FR-072KL")
      )
      (libsource (lib "Eight_bit_v1") (part "RC0805FR-072KL"))
    )
    (comp (ref "R42")
      (value "1K")
      (footprint "R0805")
      (description "RES SMD 1K OHM 1% 1/8W 0805")
      (fields
        (field (name "MANUFACTURER") "Yageo Phycomp")
        (field (name "MANUFACTURER PART NUMBER") "RC0805FR-071KL")
      )
      (libsource (lib "Eight_bit_v1") (part "RC0805FR-071KL"))
    )
    (comp (ref "R43")
      (value "1K")
      (footprint "R0805")
      (description "RES SMD 1K OHM 1% 1/8W 0805")
      (fields
        (field (name "MANUFACTURER") "Yageo Phycomp")
        (field (name "MANUFACTURER PART NUMBER") "RC0805FR-071KL")
      )
      (libsource (lib "Eight_bit_v1") (part "RC0805FR-071KL"))
    )
    (comp (ref "R44")
      (value "2K")
      (footprint "R0805")
      (description "RES SMD 2K OHM 1% 1/8W 0805")
      (fields
        (field (name "MANUFACTURER") "Yageo")
        (field (name "MANUFACTURER PART NUMBER") "RC0805FR-072KL")
      )
      (libsource (lib "Eight_bit_v1") (part "RC0805FR-072KL"))
    )
    (comp (ref "R45")
      (value "2K")
      (footprint "R0805")
      (description "RES SMD 2K OHM 1% 1/8W 0805")
      (fields
        (field (name "MANUFACTURER") "Yageo")
        (field (name "MANUFACTURER PART NUMBER") "RC0805FR-072KL")
      )
      (libsource (lib "Eight_bit_v1") (part "RC0805FR-072KL"))
    )
    (comp (ref "R46")
      (value "1K")
      (footprint "R0805")
      (description "RES SMD 1K OHM 1% 1/8W 0805")
      (fields
        (field (name "MANUFACTURER") "Yageo Phycomp")
        (field (name "MANUFACTURER PART NUMBER") "RC0805FR-071KL")
      )
      (libsource (lib "Eight_bit_v1") (part "RC0805FR-071KL"))
    )
    (comp (ref "R47")
      (value "1K")
      (footprint "R0805")
      (description "RES SMD 1K OHM 1% 1/8W 0805")
      (fields
        (field (name "MANUFACTURER") "Yageo Phycomp")
        (field (name "MANUFACTURER PART NUMBER") "RC0805FR-071KL")
      )
      (libsource (lib "Eight_bit_v1") (part "RC0805FR-071KL"))
    )
    (comp (ref "R48")
      (value "2K")
      (footprint "R0805")
      (description "RES SMD 2K OHM 1% 1/8W 0805")
      (fields
        (field (name "MANUFACTURER") "Yageo")
        (field (name "MANUFACTURER PART NUMBER") "RC0805FR-072KL")
      )
      (libsource (lib "Eight_bit_v1") (part "RC0805FR-072KL"))
    )
    (comp (ref "R49")
      (value "1K")
      (footprint "R0805")
      (description "RES SMD 1K OHM 1% 1/8W 0805")
      (fields
        (field (name "MANUFACTURER") "Yageo Phycomp")
        (field (name "MANUFACTURER PART NUMBER") "RC0805FR-071KL")
      )
      (libsource (lib "Eight_bit_v1") (part "RC0805FR-071KL"))
    )
    (comp (ref "R50")
      (value "2K")
      (footprint "R0805")
      (description "RES SMD 2K OHM 1% 1/8W 0805")
      (fields
        (field (name "MANUFACTURER") "Yageo")
        (field (name "MANUFACTURER PART NUMBER") "RC0805FR-072KL")
      )
      (libsource (lib "Eight_bit_v1") (part "RC0805FR-072KL"))
    )
    (comp (ref "R51")
      (value "2K")
      (footprint "R0805")
      (description "RES SMD 2K OHM 1% 1/8W 0805")
      (fields
        (field (name "MANUFACTURER") "Yageo")
        (field (name "MANUFACTURER PART NUMBER") "RC0805FR-072KL")
      )
      (libsource (lib "Eight_bit_v1") (part "RC0805FR-072KL"))
    )
    (comp (ref "R52")
      (value "1K")
      (footprint "R0805")
      (description "RES SMD 1K OHM 1% 1/8W 0805")
      (fields
        (field (name "MANUFACTURER") "Yageo Phycomp")
        (field (name "MANUFACTURER PART NUMBER") "RC0805FR-071KL")
      )
      (libsource (lib "Eight_bit_v1") (part "RC0805FR-071KL"))
    )
    (comp (ref "R53")
      (value "1K")
      (footprint "R0805")
      (description "RES SMD 1K OHM 1% 1/8W 0805")
      (fields
        (field (name "MANUFACTURER") "Yageo Phycomp")
        (field (name "MANUFACTURER PART NUMBER") "RC0805FR-071KL")
      )
      (libsource (lib "Eight_bit_v1") (part "RC0805FR-071KL"))
    )
    (comp (ref "R54")
      (value "2K")
      (footprint "R0805")
      (description "RES SMD 2K OHM 1% 1/8W 0805")
      (fields
        (field (name "MANUFACTURER") "Yageo")
        (field (name "MANUFACTURER PART NUMBER") "RC0805FR-072KL")
      )
      (libsource (lib "Eight_bit_v1") (part "RC0805FR-072KL"))
    )
    (comp (ref "R55")
      (value "2K")
      (footprint "R0805")
      (description "RES SMD 2K OHM 1% 1/8W 0805")
      (fields
        (field (name "MANUFACTURER") "Yageo")
        (field (name "MANUFACTURER PART NUMBER") "RC0805FR-072KL")
      )
      (libsource (lib "Eight_bit_v1") (part "RC0805FR-072KL"))
    )
    (comp (ref "R56")
      (value "1K")
      (footprint "R0805")
      (description "RES SMD 1K OHM 1% 1/8W 0805")
      (fields
        (field (name "MANUFACTURER") "Yageo Phycomp")
        (field (name "MANUFACTURER PART NUMBER") "RC0805FR-071KL")
      )
      (libsource (lib "Eight_bit_v1") (part "RC0805FR-071KL"))
    )
    (comp (ref "R57")
      (value "1K")
      (footprint "R0805")
      (description "RES SMD 1K OHM 1% 1/8W 0805")
      (fields
        (field (name "MANUFACTURER") "Yageo Phycomp")
        (field (name "MANUFACTURER PART NUMBER") "RC0805FR-071KL")
      )
      (libsource (lib "Eight_bit_v1") (part "RC0805FR-071KL"))
    )
    (comp (ref "R58")
      (value "2K")
      (footprint "R0805")
      (description "RES SMD 2K OHM 1% 1/8W 0805")
      (fields
        (field (name "MANUFACTURER") "Yageo")
        (field (name "MANUFACTURER PART NUMBER") "RC0805FR-072KL")
      )
      (libsource (lib "Eight_bit_v1") (part "RC0805FR-072KL"))
    )
    (comp (ref "R59")
      (value "2K")
      (footprint "R0805")
      (description "RES SMD 2K OHM 1% 1/8W 0805")
      (fields
        (field (name "MANUFACTURER") "Yageo")
        (field (name "MANUFACTURER PART NUMBER") "RC0805FR-072KL")
      )
      (libsource (lib "Eight_bit_v1") (part "RC0805FR-072KL"))
    )
    (comp (ref "R60")
      (value "1K")
      (footprint "R0805")
      (description "RES SMD 1K OHM 1% 1/8W 0805")
      (fields
        (field (name "MANUFACTURER") "Yageo Phycomp")
        (field (name "MANUFACTURER PART NUMBER") "RC0805FR-071KL")
      )
      (libsource (lib "Eight_bit_v1") (part "RC0805FR-071KL"))
    )
    (comp (ref "R61")
      (value "1K")
      (footprint "R0805")
      (description "RES SMD 1K OHM 1% 1/8W 0805")
      (fields
        (field (name "MANUFACTURER") "Yageo Phycomp")
        (field (name "MANUFACTURER PART NUMBER") "RC0805FR-071KL")
      )
      (libsource (lib "Eight_bit_v1") (part "RC0805FR-071KL"))
    )
    (comp (ref "R62")
      (value "2K")
      (footprint "R0805")
      (description "RES SMD 2K OHM 1% 1/8W 0805")
      (fields
        (field (name "MANUFACTURER") "Yageo")
        (field (name "MANUFACTURER PART NUMBER") "RC0805FR-072KL")
      )
      (libsource (lib "Eight_bit_v1") (part "RC0805FR-072KL"))
    )
    (comp (ref "R63")
      (value "1K")
      (footprint "R0805")
      (description "RES SMD 1K OHM 1% 1/8W 0805")
      (fields
        (field (name "MANUFACTURER") "Yageo Phycomp")
        (field (name "MANUFACTURER PART NUMBER") "RC0805FR-071KL")
      )
      (libsource (lib "Eight_bit_v1") (part "RC0805FR-071KL"))
    )
    (comp (ref "R64")
      (value "2K")
      (footprint "R0805")
      (description "RES SMD 2K OHM 1% 1/8W 0805")
      (fields
        (field (name "MANUFACTURER") "Yageo")
        (field (name "MANUFACTURER PART NUMBER") "RC0805FR-072KL")
      )
      (libsource (lib "Eight_bit_v1") (part "RC0805FR-072KL"))
    )
    (comp (ref "R65")
      (value "10K")
      (footprint "R0805")
      (description "RES SMD 10K OHM 1% 1/8W 0805")
      (fields
        (field (name "MANUFACTURER") "Yageo")
        (field (name "MANUFACTURER PART NUMBER") "RC0805FR-0710KL")
      )
      (libsource (lib "Eight_bit_v1") (part "RC0805FR-0710KL"))
    )
    (comp (ref "R66")
      (value "10K")
      (footprint "R0805")
      (description "RES SMD 10K OHM 1% 1/8W 0805")
      (fields
        (field (name "MANUFACTURER") "Yageo")
        (field (name "MANUFACTURER PART NUMBER") "RC0805FR-0710KL")
      )
      (libsource (lib "Eight_bit_v1") (part "RC0805FR-0710KL"))
    )
    (comp (ref "R67")
      (value "10K")
      (footprint "R0805")
      (description "RES SMD 10K OHM 1% 1/8W 0805")
      (fields
        (field (name "MANUFACTURER") "Yageo")
        (field (name "MANUFACTURER PART NUMBER") "RC0805FR-0710KL")
      )
      (libsource (lib "Eight_bit_v1") (part "RC0805FR-0710KL"))
    )
    (comp (ref "R68")
      (value "220R")
      (footprint "R0805")
      (description "RES SMD 220 OHM 1% 1/8W 0805")
      (fields
        (field (name "MANUFACTURER") "Yageo")
        (field (name "MANUFACTURER PART NUMBER") "RC0805FR-07220RL")
      )
      (libsource (lib "Eight_bit_v1") (part "RC0805FR-07220RL"))
    )
    (comp (ref "R69")
      (value "220R")
      (footprint "R0805")
      (description "RES SMD 220 OHM 1% 1/8W 0805")
      (fields
        (field (name "MANUFACTURER") "Yageo")
        (field (name "MANUFACTURER PART NUMBER") "RC0805FR-07220RL")
      )
      (libsource (lib "Eight_bit_v1") (part "RC0805FR-07220RL"))
    )
    (comp (ref "R70")
      (value "10K")
      (footprint "R0805")
      (description "RES SMD 10K OHM 1% 1/8W 0805")
      (fields
        (field (name "MANUFACTURER") "Yageo")
        (field (name "MANUFACTURER PART NUMBER") "RC0805FR-0710KL")
      )
      (libsource (lib "Eight_bit_v1") (part "RC0805FR-0710KL"))
    )
    (comp (ref "R71")
      (value "220R")
      (footprint "R0805")
      (description "RES SMD 220 OHM 1% 1/8W 0805")
      (fields
        (field (name "MANUFACTURER") "Yageo")
        (field (name "MANUFACTURER PART NUMBER") "RC0805FR-07220RL")
      )
      (libsource (lib "Eight_bit_v1") (part "RC0805FR-07220RL"))
    )
    (comp (ref "R72")
      (value "220R")
      (footprint "R0805")
      (description "RES SMD 220 OHM 1% 1/8W 0805")
      (fields
        (field (name "MANUFACTURER") "Yageo")
        (field (name "MANUFACTURER PART NUMBER") "RC0805FR-07220RL")
      )
      (libsource (lib "Eight_bit_v1") (part "RC0805FR-07220RL"))
    )
    (comp (ref "R73")
      (value "220R")
      (footprint "R0805")
      (description "RES SMD 220 OHM 1% 1/8W 0805")
      (fields
        (field (name "MANUFACTURER") "Yageo")
        (field (name "MANUFACTURER PART NUMBER") "RC0805FR-07220RL")
      )
      (libsource (lib "Eight_bit_v1") (part "RC0805FR-07220RL"))
    )
    (comp (ref "R74")
      (value "220R")
      (footprint "R0805")
      (description "RES SMD 220 OHM 1% 1/8W 0805")
      (fields
        (field (name "MANUFACTURER") "Yageo")
        (field (name "MANUFACTURER PART NUMBER") "RC0805FR-07220RL")
      )
      (libsource (lib "Eight_bit_v1") (part "RC0805FR-07220RL"))
    )
    (comp (ref "R75")
      (value "220R")
      (footprint "R0805")
      (description "RES SMD 220 OHM 1% 1/8W 0805")
      (fields
        (field (name "MANUFACTURER") "Yageo")
        (field (name "MANUFACTURER PART NUMBER") "RC0805FR-07220RL")
      )
      (libsource (lib "Eight_bit_v1") (part "RC0805FR-07220RL"))
    )
    (comp (ref "R76")
      (value "220R")
      (footprint "R0805")
      (description "RES SMD 220 OHM 1% 1/8W 0805")
      (fields
        (field (name "MANUFACTURER") "Yageo")
        (field (name "MANUFACTURER PART NUMBER") "RC0805FR-07220RL")
      )
      (libsource (lib "Eight_bit_v1") (part "RC0805FR-07220RL"))
    )
    (comp (ref "R77")
      (value "220R")
      (footprint "R0805")
      (description "RES SMD 220 OHM 1% 1/8W 0805")
      (fields
        (field (name "MANUFACTURER") "Yageo")
        (field (name "MANUFACTURER PART NUMBER") "RC0805FR-07220RL")
      )
      (libsource (lib "Eight_bit_v1") (part "RC0805FR-07220RL"))
    )
    (comp (ref "R78")
      (value "220R")
      (footprint "R0805")
      (description "RES SMD 220 OHM 1% 1/8W 0805")
      (fields
        (field (name "MANUFACTURER") "Yageo")
        (field (name "MANUFACTURER PART NUMBER") "RC0805FR-07220RL")
      )
      (libsource (lib "Eight_bit_v1") (part "RC0805FR-07220RL"))
    )
    (comp (ref "R79")
      (value "220R")
      (footprint "R0805")
      (description "RES SMD 220 OHM 1% 1/8W 0805")
      (fields
        (field (name "MANUFACTURER") "Yageo")
        (field (name "MANUFACTURER PART NUMBER") "RC0805FR-07220RL")
      )
      (libsource (lib "Eight_bit_v1") (part "RC0805FR-07220RL"))
    )
    (comp (ref "R80")
      (value "220R")
      (footprint "R0805")
      (description "RES SMD 220 OHM 1% 1/8W 0805")
      (fields
        (field (name "MANUFACTURER") "Yageo")
        (field (name "MANUFACTURER PART NUMBER") "RC0805FR-07220RL")
      )
      (libsource (lib "Eight_bit_v1") (part "RC0805FR-07220RL"))
    )
    (comp (ref "R81")
      (value "220R")
      (footprint "R0805")
      (description "RES SMD 220 OHM 1% 1/8W 0805")
      (fields
        (field (name "MANUFACTURER") "Yageo")
        (field (name "MANUFACTURER PART NUMBER") "RC0805FR-07220RL")
      )
      (libsource (lib "Eight_bit_v1") (part "RC0805FR-07220RL"))
    )
    (comp (ref "R82")
      (value "220R")
      (footprint "R0805")
      (description "RES SMD 220 OHM 1% 1/8W 0805")
      (fields
        (field (name "MANUFACTURER") "Yageo")
        (field (name "MANUFACTURER PART NUMBER") "RC0805FR-07220RL")
      )
      (libsource (lib "Eight_bit_v1") (part "RC0805FR-07220RL"))
    )
    (comp (ref "R83")
      (value "220R")
      (footprint "R0805")
      (description "RES SMD 220 OHM 1% 1/8W 0805")
      (fields
        (field (name "MANUFACTURER") "Yageo")
        (field (name "MANUFACTURER PART NUMBER") "RC0805FR-07220RL")
      )
      (libsource (lib "Eight_bit_v1") (part "RC0805FR-07220RL"))
    )
    (comp (ref "R84")
      (value "220R")
      (footprint "R0805")
      (description "RES SMD 220 OHM 1% 1/8W 0805")
      (fields
        (field (name "MANUFACTURER") "Yageo")
        (field (name "MANUFACTURER PART NUMBER") "RC0805FR-07220RL")
      )
      (libsource (lib "Eight_bit_v1") (part "RC0805FR-07220RL"))
    )
    (comp (ref "R85")
      (value "220R")
      (footprint "R0805")
      (description "RES SMD 220 OHM 1% 1/8W 0805")
      (fields
        (field (name "MANUFACTURER") "Yageo")
        (field (name "MANUFACTURER PART NUMBER") "RC0805FR-07220RL")
      )
      (libsource (lib "Eight_bit_v1") (part "RC0805FR-07220RL"))
    )
    (comp (ref "R86")
      (value "220R")
      (footprint "R0805")
      (description "RES SMD 220 OHM 1% 1/8W 0805")
      (fields
        (field (name "MANUFACTURER") "Yageo")
        (field (name "MANUFACTURER PART NUMBER") "RC0805FR-07220RL")
      )
      (libsource (lib "Eight_bit_v1") (part "RC0805FR-07220RL"))
    )
    (comp (ref "R87")
      (value "220R")
      (footprint "R0805")
      (description "RES SMD 220 OHM 1% 1/8W 0805")
      (fields
        (field (name "MANUFACTURER") "Yageo")
        (field (name "MANUFACTURER PART NUMBER") "RC0805FR-07220RL")
      )
      (libsource (lib "Eight_bit_v1") (part "RC0805FR-07220RL"))
    )
    (comp (ref "R88")
      (value "220R")
      (footprint "R0805")
      (description "RES SMD 220 OHM 1% 1/8W 0805")
      (fields
        (field (name "MANUFACTURER") "Yageo")
        (field (name "MANUFACTURER PART NUMBER") "RC0805FR-07220RL")
      )
      (libsource (lib "Eight_bit_v1") (part "RC0805FR-07220RL"))
    )
    (comp (ref "R89")
      (value "220R")
      (footprint "R0805")
      (description "RES SMD 220 OHM 1% 1/8W 0805")
      (fields
        (field (name "MANUFACTURER") "Yageo")
        (field (name "MANUFACTURER PART NUMBER") "RC0805FR-07220RL")
      )
      (libsource (lib "Eight_bit_v1") (part "RC0805FR-07220RL"))
    )
    (comp (ref "R90")
      (value "220R")
      (footprint "R0805")
      (description "RES SMD 220 OHM 1% 1/8W 0805")
      (fields
        (field (name "MANUFACTURER") "Yageo")
        (field (name "MANUFACTURER PART NUMBER") "RC0805FR-07220RL")
      )
      (libsource (lib "Eight_bit_v1") (part "RC0805FR-07220RL"))
    )
    (comp (ref "R91")
      (value "220R")
      (footprint "R0805")
      (description "RES SMD 220 OHM 1% 1/8W 0805")
      (fields
        (field (name "MANUFACTURER") "Yageo")
        (field (name "MANUFACTURER PART NUMBER") "RC0805FR-07220RL")
      )
      (libsource (lib "Eight_bit_v1") (part "RC0805FR-07220RL"))
    )
    (comp (ref "R92")
      (value "220R")
      (footprint "R0805")
      (description "RES SMD 220 OHM 1% 1/8W 0805")
      (fields
        (field (name "MANUFACTURER") "Yageo")
        (field (name "MANUFACTURER PART NUMBER") "RC0805FR-07220RL")
      )
      (libsource (lib "Eight_bit_v1") (part "RC0805FR-07220RL"))
    )
    (comp (ref "R93")
      (value "220R")
      (footprint "R0805")
      (description "RES SMD 220 OHM 1% 1/8W 0805")
      (fields
        (field (name "MANUFACTURER") "Yageo")
        (field (name "MANUFACTURER PART NUMBER") "RC0805FR-07220RL")
      )
      (libsource (lib "Eight_bit_v1") (part "RC0805FR-07220RL"))
    )
    (comp (ref "R94")
      (value "220R")
      (footprint "R0805")
      (description "RES SMD 220 OHM 1% 1/8W 0805")
      (fields
        (field (name "MANUFACTURER") "Yageo")
        (field (name "MANUFACTURER PART NUMBER") "RC0805FR-07220RL")
      )
      (libsource (lib "Eight_bit_v1") (part "RC0805FR-07220RL"))
    )
    (comp (ref "R95")
      (value "220R")
      (footprint "R0805")
      (description "RES SMD 220 OHM 1% 1/8W 0805")
      (fields
        (field (name "MANUFACTURER") "Yageo")
        (field (name "MANUFACTURER PART NUMBER") "RC0805FR-07220RL")
      )
      (libsource (lib "Eight_bit_v1") (part "RC0805FR-07220RL"))
    )
    (comp (ref "R96")
      (value "220R")
      (footprint "R0805")
      (description "RES SMD 220 OHM 1% 1/8W 0805")
      (fields
        (field (name "MANUFACTURER") "Yageo")
        (field (name "MANUFACTURER PART NUMBER") "RC0805FR-07220RL")
      )
      (libsource (lib "Eight_bit_v1") (part "RC0805FR-07220RL"))
    )
    (comp (ref "R97")
      (value "220R")
      (footprint "R0805")
      (description "RES SMD 220 OHM 1% 1/8W 0805")
      (fields
        (field (name "MANUFACTURER") "Yageo")
        (field (name "MANUFACTURER PART NUMBER") "RC0805FR-07220RL")
      )
      (libsource (lib "Eight_bit_v1") (part "RC0805FR-07220RL"))
    )
    (comp (ref "R98")
      (value "220R")
      (footprint "R0805")
      (description "RES SMD 220 OHM 1% 1/8W 0805")
      (fields
        (field (name "MANUFACTURER") "Yageo")
        (field (name "MANUFACTURER PART NUMBER") "RC0805FR-07220RL")
      )
      (libsource (lib "Eight_bit_v1") (part "RC0805FR-07220RL"))
    )
    (comp (ref "R99")
      (value "220R")
      (footprint "R0805")
      (description "RES SMD 220 OHM 1% 1/8W 0805")
      (fields
        (field (name "MANUFACTURER") "Yageo")
        (field (name "MANUFACTURER PART NUMBER") "RC0805FR-07220RL")
      )
      (libsource (lib "Eight_bit_v1") (part "RC0805FR-07220RL"))
    )
    (comp (ref "R100")
      (value "220R")
      (footprint "R0805")
      (description "RES SMD 220 OHM 1% 1/8W 0805")
      (fields
        (field (name "MANUFACTURER") "Yageo")
        (field (name "MANUFACTURER PART NUMBER") "RC0805FR-07220RL")
      )
      (libsource (lib "Eight_bit_v1") (part "RC0805FR-07220RL"))
    )
    (comp (ref "R101")
      (value "1K")
      (footprint "R0805")
      (description "RES SMD 1K OHM 1% 1/8W 0805")
      (fields
        (field (name "MANUFACTURER") "Yageo Phycomp")
        (field (name "MANUFACTURER PART NUMBER") "RC0805FR-071KL")
      )
      (libsource (lib "Eight_bit_v1") (part "RC0805FR-071KL"))
    )
    (comp (ref "R102")
      (value "1K")
      (footprint "R0805")
      (description "RES SMD 1K OHM 1% 1/8W 0805")
      (fields
        (field (name "MANUFACTURER") "Yageo Phycomp")
        (field (name "MANUFACTURER PART NUMBER") "RC0805FR-071KL")
      )
      (libsource (lib "Eight_bit_v1") (part "RC0805FR-071KL"))
    )
    (comp (ref "R103")
      (value "1K")
      (footprint "R0805")
      (description "RES SMD 1K OHM 1% 1/8W 0805")
      (fields
        (field (name "MANUFACTURER") "Yageo Phycomp")
        (field (name "MANUFACTURER PART NUMBER") "RC0805FR-071KL")
      )
      (libsource (lib "Eight_bit_v1") (part "RC0805FR-071KL"))
    )
    (comp (ref "R104")
      (value "220R")
      (footprint "R0805")
      (description "RES SMD 220 OHM 1% 1/8W 0805")
      (fields
        (field (name "MANUFACTURER") "Yageo")
        (field (name "MANUFACTURER PART NUMBER") "RC0805FR-07220RL")
      )
      (libsource (lib "Eight_bit_v1") (part "RC0805FR-07220RL"))
    )
    (comp (ref "R105")
      (value "220R")
      (footprint "R0805")
      (description "RES SMD 220 OHM 1% 1/8W 0805")
      (fields
        (field (name "MANUFACTURER") "Yageo")
        (field (name "MANUFACTURER PART NUMBER") "RC0805FR-07220RL")
      )
      (libsource (lib "Eight_bit_v1") (part "RC0805FR-07220RL"))
    )
    (comp (ref "R106")
      (value "220R")
      (footprint "R0805")
      (description "RES SMD 220 OHM 1% 1/8W 0805")
      (fields
        (field (name "MANUFACTURER") "Yageo")
        (field (name "MANUFACTURER PART NUMBER") "RC0805FR-07220RL")
      )
      (libsource (lib "Eight_bit_v1") (part "RC0805FR-07220RL"))
    )
    (comp (ref "R107")
      (value "220R")
      (footprint "R0805")
      (description "RES SMD 220 OHM 1% 1/8W 0805")
      (fields
        (field (name "MANUFACTURER") "Yageo")
        (field (name "MANUFACTURER PART NUMBER") "RC0805FR-07220RL")
      )
      (libsource (lib "Eight_bit_v1") (part "RC0805FR-07220RL"))
    )
    (comp (ref "R108")
      (value "220R")
      (footprint "R0805")
      (description "RES SMD 220 OHM 1% 1/8W 0805")
      (fields
        (field (name "MANUFACTURER") "Yageo")
        (field (name "MANUFACTURER PART NUMBER") "RC0805FR-07220RL")
      )
      (libsource (lib "Eight_bit_v1") (part "RC0805FR-07220RL"))
    )
    (comp (ref "R109")
      (value "220R")
      (footprint "R0805")
      (description "RES SMD 220 OHM 1% 1/8W 0805")
      (fields
        (field (name "MANUFACTURER") "Yageo")
        (field (name "MANUFACTURER PART NUMBER") "RC0805FR-07220RL")
      )
      (libsource (lib "Eight_bit_v1") (part "RC0805FR-07220RL"))
    )
    (comp (ref "R110")
      (value "220R")
      (footprint "R0805")
      (description "RES SMD 220 OHM 1% 1/8W 0805")
      (fields
        (field (name "MANUFACTURER") "Yageo")
        (field (name "MANUFACTURER PART NUMBER") "RC0805FR-07220RL")
      )
      (libsource (lib "Eight_bit_v1") (part "RC0805FR-07220RL"))
    )
    (comp (ref "R111")
      (value "220R")
      (footprint "R0805")
      (description "RES SMD 220 OHM 1% 1/8W 0805")
      (fields
        (field (name "MANUFACTURER") "Yageo")
        (field (name "MANUFACTURER PART NUMBER") "RC0805FR-07220RL")
      )
      (libsource (lib "Eight_bit_v1") (part "RC0805FR-07220RL"))
    )
    (comp (ref "R112")
      (value "220R")
      (footprint "R0805")
      (description "RES SMD 220 OHM 1% 1/8W 0805")
      (fields
        (field (name "MANUFACTURER") "Yageo")
        (field (name "MANUFACTURER PART NUMBER") "RC0805FR-07220RL")
      )
      (libsource (lib "Eight_bit_v1") (part "RC0805FR-07220RL"))
    )
    (comp (ref "R113")
      (value "220R")
      (footprint "R0805")
      (description "RES SMD 220 OHM 1% 1/8W 0805")
      (fields
        (field (name "MANUFACTURER") "Yageo")
        (field (name "MANUFACTURER PART NUMBER") "RC0805FR-07220RL")
      )
      (libsource (lib "Eight_bit_v1") (part "RC0805FR-07220RL"))
    )
    (comp (ref "R114")
      (value "220R")
      (footprint "R0805")
      (description "RES SMD 220 OHM 1% 1/8W 0805")
      (fields
        (field (name "MANUFACTURER") "Yageo")
        (field (name "MANUFACTURER PART NUMBER") "RC0805FR-07220RL")
      )
      (libsource (lib "Eight_bit_v1") (part "RC0805FR-07220RL"))
    )
    (comp (ref "R115")
      (value "220R")
      (footprint "R0805")
      (description "RES SMD 220 OHM 1% 1/8W 0805")
      (fields
        (field (name "MANUFACTURER") "Yageo")
        (field (name "MANUFACTURER PART NUMBER") "RC0805FR-07220RL")
      )
      (libsource (lib "Eight_bit_v1") (part "RC0805FR-07220RL"))
    )
    (comp (ref "R116")
      (value "220R")
      (footprint "R0805")
      (description "RES SMD 220 OHM 1% 1/8W 0805")
      (fields
        (field (name "MANUFACTURER") "Yageo")
        (field (name "MANUFACTURER PART NUMBER") "RC0805FR-07220RL")
      )
      (libsource (lib "Eight_bit_v1") (part "RC0805FR-07220RL"))
    )
    (comp (ref "R117")
      (value "220R")
      (footprint "R0805")
      (description "RES SMD 220 OHM 1% 1/8W 0805")
      (fields
        (field (name "MANUFACTURER") "Yageo")
        (field (name "MANUFACTURER PART NUMBER") "RC0805FR-07220RL")
      )
      (libsource (lib "Eight_bit_v1") (part "RC0805FR-07220RL"))
    )
    (comp (ref "S1")
      (value "DIP")
      (footprint "BDB04")
      (description "Switch")
      (fields
        (field (name "MANUFACTURER_PART_NUMBER") "BDB04")
        (field (name "MOUSER PART NUMBER") "611-BDB04")
      )
      (libsource (lib "Eight_bit_v1") (part "BDB04"))
    )
    (comp (ref "S2")
      (value "DIP")
      (footprint "BDB04")
      (description "Switch")
      (fields
        (field (name "MANUFACTURER_PART_NUMBER") "BDB04")
        (field (name "MOUSER PART NUMBER") "611-BDB04")
      )
      (libsource (lib "Eight_bit_v1") (part "BDB04"))
    )
    (comp (ref "S3")
      (value "DIP")
      (footprint "BDB04")
      (description "Switch")
      (fields
        (field (name "MANUFACTURER_PART_NUMBER") "BDB04")
        (field (name "MOUSER PART NUMBER") "611-BDB04")
      )
      (libsource (lib "Eight_bit_v1") (part "BDB04"))
    )
    (comp (ref "SW1")
      (value "1825159-1")
      (footprint "*SW_1825159-1")
      (description "STS121PC04=SPDT SLIDE SWITCH")
      (fields (field (name "MF") "TE Connectivity"))
      (libsource (lib "Eight_bit_v1") (part "1825159-1"))
    )
    (comp (ref "SW2")
      (value "1825159-1")
      (footprint "*SW_1825159-1")
      (description "STS121PC04=SPDT SLIDE SWITCH")
      (fields (field (name "MF") "TE Connectivity"))
      (libsource (lib "Eight_bit_v1") (part "1825159-1"))
    )
    (comp (ref "SW3")
      (value "1825159-1")
      (footprint "*SW_1825159-1")
      (description "STS121PC04=SPDT SLIDE SWITCH")
      (fields (field (name "MF") "TE Connectivity"))
      (libsource (lib "Eight_bit_v1") (part "1825159-1"))
    )
    (comp (ref "SW4")
      (value "1825910-6")
      (footprint "1825910-6")
      (description "ALCOSWITCH - TE CONNECTIVITY - 1825910-6 - TACT SWITCH, SPST, 0.05A, 24VDC, SOLDER")
      (fields (field (name "MANUFACTURER") "TE Connectivity Alcoswitch"))
      (libsource (lib "Eight_bit_v1") (part "1825910-6"))
    )
    (comp (ref "SW5")
      (value "1825910-6")
      (footprint "1825910-6")
      (description "ALCOSWITCH - TE CONNECTIVITY - 1825910-6 - TACT SWITCH, SPST, 0.05A, 24VDC, SOLDER")
      (fields (field (name "MANUFACTURER") "TE Connectivity Alcoswitch"))
      (libsource (lib "Eight_bit_v1") (part "1825910-6"))
    )
    (comp (ref "SW6")
      (value "1825910-6")
      (footprint "1825910-6")
      (description "ALCOSWITCH - TE CONNECTIVITY - 1825910-6 - TACT SWITCH, SPST, 0.05A, 24VDC, SOLDER")
      (fields (field (name "MANUFACTURER") "TE Connectivity Alcoswitch"))
      (libsource (lib "Eight_bit_v1") (part "1825910-6"))
    )
    (comp (ref "U1")
      (value "LM1117T-3.3V")
      (footprint "KC03")
      (description "TEXAS INSTRUMENTS         LM1117T-3.3/NOPB            IC, LDO VOLT REG, 0.8A, 3.3V, TO220-3")
      (fields
        (field (name "MANUFACTURER") "TI National Semiconductor")
        (field (name "MANUFACTURER PART NUMBER") "LM1117T-3.3/NOPB")
      )
      (libsource (lib "Eight_bit_v1") (part "LM1117T-3.3/NOPB"))
    )
    (comp (ref "U2")
      (value "CAT28C16")
      (footprint "Eight_bit_v1:DIP254P1524X635-24")
      (description "Integrated Circuit")
      (fields (field (name "MANUFACTURER_PART_NUMBER") "CAT28C16ALI-20"))
      (libsource (lib "Eight_bit_v1") (part "CAT28C16ALI-20"))
    )
    (comp (ref "U3")
      (value "74LS189")
      (footprint "DIP762W60P254L1975H445Q16N")
      (libsource (lib "Eight_bit_v1") (part "74LS189"))
    )
    (comp (ref "U4")
      (value "CAT28C16")
      (footprint "Eight_bit_v1:DIP254P1524X635-24")
      (description "Integrated Circuit")
      (fields (field (name "MANUFACTURER_PART_NUMBER") "CAT28C16ALI-20"))
      (libsource (lib "Eight_bit_v1") (part "CAT28C16ALI-20"))
    )
    (comp (ref "U5")
      (value "74LS189")
      (footprint "DIP762W60P254L1975H445Q16N")
      (libsource (lib "Eight_bit_v1") (part "74LS189"))
    )
    (comp (ref "U6")
      (value "EPM1270T144C5N")
      (footprint "TQFP144_M")
      (libsource (lib "") (part "EPM1270T144C5N_1"))
    )
    (comp (ref "U7")
      (value "SC52-11HWA")
      (footprint "*LED_SC52-11HWA")
      (description "Display: LED; single 7-segment; 13.2mm; red; 0.9-2.2mcd")
      (fields (field (name "MF") "Kingbright"))
      (libsource (lib "SC52-11HWA") (part "SC52-11HWA"))
    )
    (comp (ref "U8")
      (value "SC52-11HWA")
      (footprint "*LED_SC52-11HWA")
      (description "Display: LED; single 7-segment; 13.2mm; red; 0.9-2.2mcd")
      (fields (field (name "MF") "Kingbright"))
      (libsource (lib "SC52-11HWA") (part "SC52-11HWA"))
    )
    (comp (ref "U9")
      (value "SC52-11HWA")
      (footprint "*LED_SC52-11HWA")
      (description "Display: LED; single 7-segment; 13.2mm; red; 0.9-2.2mcd")
      (fields (field (name "MF") "Kingbright"))
      (libsource (lib "SC52-11HWA") (part "SC52-11HWA"))
    )
    (comp (ref "U10")
      (value "SC52-11HWA")
      (footprint "*LED_SC52-11HWA")
      (description "Display: LED; single 7-segment; 13.2mm; red; 0.9-2.2mcd")
      (fields (field (name "MF") "Kingbright"))
      (libsource (lib "SC52-11HWA") (part "SC52-11HWA"))
    )
    (comp (ref "Y1")
      (value "ECS-TXO-5032-120-TR")
      (footprint "*OSC_ECS-TXO-5032-120-TR")
      (fields (field (name "MF") "ECS Inc."))
      (libsource (lib "ECS-TXO-5032-120-TR") (part "ECS-TXO-5032-120-TR"))
    )
  )
  (nets
    (net (code "1") (name "+3V3") (class "Default")
      (node (ref "C2") (pin "1") (pinfunction "1_1") (pintype "passive"))
      (node (ref "C4") (pin "2") (pinfunction "2_2") (pintype "passive"))
      (node (ref "C6") (pin "2") (pinfunction "2_2") (pintype "passive"))
      (node (ref "C7") (pin "2") (pinfunction "2_2") (pintype "passive"))
      (node (ref "C8") (pin "2") (pinfunction "2_2") (pintype "passive"))
      (node (ref "C9") (pin "2") (pinfunction "2_2") (pintype "passive"))
      (node (ref "J2") (pin "4") (pinfunction "4_4") (pintype "passive"))
      (node (ref "J3") (pin "1") (pinfunction "1_1") (pintype "passive"))
      (node (ref "J3") (pin "6") (pinfunction "6_6") (pintype "passive"))
      (node (ref "R1") (pin "2") (pinfunction "2_2") (pintype "passive"))
      (node (ref "R65") (pin "2") (pinfunction "2_2") (pintype "passive"))
      (node (ref "R66") (pin "2") (pinfunction "2_2") (pintype "passive"))
      (node (ref "R67") (pin "2") (pinfunction "2_2") (pintype "passive"))
      (node (ref "S1") (pin "5") (pinfunction "NO_1_5") (pintype "passive"))
      (node (ref "S1") (pin "6") (pinfunction "NO_2_6") (pintype "passive"))
      (node (ref "S1") (pin "7") (pinfunction "NO_3_7") (pintype "passive"))
      (node (ref "S1") (pin "8") (pinfunction "NO_4_8") (pintype "passive"))
      (node (ref "S2") (pin "5") (pinfunction "NO_1_5") (pintype "passive"))
      (node (ref "S2") (pin "6") (pinfunction "NO_2_6") (pintype "passive"))
      (node (ref "S2") (pin "7") (pinfunction "NO_3_7") (pintype "passive"))
      (node (ref "S2") (pin "8") (pinfunction "NO_4_8") (pintype "passive"))
      (node (ref "S3") (pin "5") (pinfunction "NO_1_5") (pintype "passive"))
      (node (ref "S3") (pin "6") (pinfunction "NO_2_6") (pintype "passive"))
      (node (ref "S3") (pin "7") (pinfunction "NO_3_7") (pintype "passive"))
      (node (ref "S3") (pin "8") (pinfunction "NO_4_8") (pintype "passive"))
      (node (ref "SW1") (pin "1") (pinfunction "1_1") (pintype "passive"))
      (node (ref "SW2") (pin "1") (pinfunction "1_1") (pintype "passive"))
      (node (ref "SW3") (pin "1") (pinfunction "1_1") (pintype "passive"))
      (node (ref "SW4") (pin "3") (pintype "passive"))
      (node (ref "SW4") (pin "4") (pintype "passive"))
      (node (ref "SW5") (pin "3") (pintype "passive"))
      (node (ref "SW5") (pin "4") (pintype "passive"))
      (node (ref "SW6") (pin "3") (pintype "passive"))
      (node (ref "SW6") (pin "4") (pintype "passive"))
      (node (ref "U1") (pin "2") (pinfunction "VOUT_2") (pintype "power_in"))
      (node (ref "U10") (pin "3") (pinfunction "C@1_3") (pintype "passive"))
      (node (ref "U10") (pin "5") (pinfunction "DP_5") (pintype "passive"))
      (node (ref "U10") (pin "8") (pinfunction "C@2_8") (pintype "passive"))
      (node (ref "U6") (pin "100") (pinfunction "VCCIO3_100") (pintype "power_in"))
      (node (ref "U6") (pin "116") (pinfunction "VCCIO2_116") (pintype "power_in"))
      (node (ref "U6") (pin "126") (pinfunction "VCCINT_126") (pintype "power_in"))
      (node (ref "U6") (pin "136") (pinfunction "VCCIO2_136") (pintype "power_in"))
      (node (ref "U6") (pin "19") (pinfunction "VCCINT_19") (pintype "power_in"))
      (node (ref "U6") (pin "25") (pinfunction "VCCIO1_25") (pintype "power_in"))
      (node (ref "U6") (pin "46") (pinfunction "VCCIO4_46") (pintype "power_in"))
      (node (ref "U6") (pin "56") (pinfunction "VCCINT_56") (pintype "power_in"))
      (node (ref "U6") (pin "64") (pinfunction "VCCIO4_64") (pintype "power_in"))
      (node (ref "U6") (pin "82") (pinfunction "VCCIO3_82") (pintype "power_in"))
      (node (ref "U6") (pin "9") (pinfunction "VCCIO1_9") (pintype "power_in"))
      (node (ref "U6") (pin "90") (pinfunction "VCCINT_90") (pintype "power_in"))
      (node (ref "U7") (pin "3") (pinfunction "C@1_3") (pintype "passive"))
      (node (ref "U7") (pin "5") (pinfunction "DP_5") (pintype "passive"))
      (node (ref "U7") (pin "8") (pinfunction "C@2_8") (pintype "passive"))
      (node (ref "U8") (pin "3") (pinfunction "C@1_3") (pintype "passive"))
      (node (ref "U8") (pin "5") (pinfunction "DP_5") (pintype "passive"))
      (node (ref "U8") (pin "8") (pinfunction "C@2_8") (pintype "passive"))
      (node (ref "U9") (pin "3") (pinfunction "C@1_3") (pintype "passive"))
      (node (ref "U9") (pin "5") (pinfunction "DP_5") (pintype "passive"))
      (node (ref "U9") (pin "8") (pinfunction "C@2_8") (pintype "passive"))
      (node (ref "Y1") (pin "4") (pinfunction "VDD_4") (pintype "input"))
    )
    (net (code "2") (name "+5V") (class "Default")
      (node (ref "C1") (pin "1") (pinfunction "1_1") (pintype "passive"))
      (node (ref "C10") (pin "2") (pinfunction "2_2") (pintype "passive"))
      (node (ref "C11") (pin "2") (pinfunction "2_2") (pintype "passive"))
      (node (ref "C12") (pin "2") (pinfunction "2_2") (pintype "passive"))
      (node (ref "C13") (pin "2") (pinfunction "2_2") (pintype "passive"))
      (node (ref "C3") (pin "2") (pinfunction "2_2") (pintype "passive"))
      (node (ref "J1") (pin "1") (pinfunction "1_1") (pintype "passive"))
      (node (ref "J3") (pin "3") (pinfunction "3_3") (pintype "passive"))
      (node (ref "J3") (pin "5") (pinfunction "5_5") (pintype "passive"))
      (node (ref "U1") (pin "3") (pinfunction "VIN_3") (pintype "power_in"))
      (node (ref "U2") (pin "21") (pinfunction "~WE_21") (pintype "passive"))
      (node (ref "U2") (pin "24") (pinfunction "VCC_24") (pintype "passive"))
      (node (ref "U3") (pin "16") (pinfunction "VCC_16") (pintype "passive"))
      (node (ref "U4") (pin "1") (pinfunction "A7_1") (pintype "passive"))
      (node (ref "U4") (pin "21") (pinfunction "~WE_21") (pintype "passive"))
      (node (ref "U4") (pin "24") (pinfunction "VCC_24") (pintype "passive"))
      (node (ref "U5") (pin "16") (pinfunction "VCC_16") (pintype "passive"))
    )
    (net (code "3") (name "/A0_LED") (class "Default")
      (node (ref "D18") (pin "2") (pinfunction "Anode_2") (pintype "passive"))
      (node (ref "U6") (pin "12") (pinfunction "IO_12") (pintype "bidirectional"))
    )
    (net (code "4") (name "/A1_LED") (class "Default")
      (node (ref "D19") (pin "2") (pinfunction "Anode_2") (pintype "passive"))
      (node (ref "U6") (pin "11") (pinfunction "IO_11") (pintype "bidirectional"))
    )
    (net (code "5") (name "/A2_LED") (class "Default")
      (node (ref "D20") (pin "2") (pinfunction "Anode_2") (pintype "passive"))
      (node (ref "U6") (pin "8") (pinfunction "IO_8") (pintype "bidirectional"))
    )
    (net (code "6") (name "/A3_LED") (class "Default")
      (node (ref "D21") (pin "2") (pinfunction "Anode_2") (pintype "passive"))
      (node (ref "U6") (pin "7") (pinfunction "IO_7") (pintype "bidirectional"))
    )
    (net (code "7") (name "/A4_LED") (class "Default")
      (node (ref "D22") (pin "2") (pinfunction "Anode_2") (pintype "passive"))
      (node (ref "U6") (pin "6") (pinfunction "IO_6") (pintype "bidirectional"))
    )
    (net (code "8") (name "/A5_LED") (class "Default")
      (node (ref "D23") (pin "2") (pinfunction "Anode_2") (pintype "passive"))
      (node (ref "U6") (pin "5") (pinfunction "IO_5") (pintype "bidirectional"))
    )
    (net (code "9") (name "/A6_LED") (class "Default")
      (node (ref "D24") (pin "2") (pinfunction "Anode_2") (pintype "passive"))
      (node (ref "U6") (pin "4") (pinfunction "IO_4") (pintype "bidirectional"))
    )
    (net (code "10") (name "/A7_LED") (class "Default")
      (node (ref "D25") (pin "2") (pinfunction "Anode_2") (pintype "passive"))
      (node (ref "U6") (pin "3") (pinfunction "IO_3") (pintype "bidirectional"))
    )
    (net (code "11") (name "/AD_SW_0") (class "Default")
      (node (ref "R2") (pin "2") (pinfunction "2_2") (pintype "passive"))
      (node (ref "S1") (pin "1") (pinfunction "COM_1_1") (pintype "passive"))
      (node (ref "U6") (pin "88") (pinfunction "IO_88") (pintype "bidirectional"))
    )
    (net (code "12") (name "/AD_SW_1") (class "Default")
      (node (ref "R3") (pin "2") (pinfunction "2_2") (pintype "passive"))
      (node (ref "S1") (pin "2") (pinfunction "COM_2_2") (pintype "passive"))
      (node (ref "U6") (pin "87") (pinfunction "IO_87") (pintype "bidirectional"))
    )
    (net (code "13") (name "/AD_SW_2") (class "Default")
      (node (ref "R4") (pin "2") (pinfunction "2_2") (pintype "passive"))
      (node (ref "S1") (pin "3") (pinfunction "COM_3_3") (pintype "passive"))
      (node (ref "U6") (pin "86") (pinfunction "IO_86") (pintype "bidirectional"))
    )
    (net (code "14") (name "/AD_SW_3") (class "Default")
      (node (ref "R5") (pin "2") (pinfunction "2_2") (pintype "passive"))
      (node (ref "S1") (pin "4") (pinfunction "COM_4_4") (pintype "passive"))
      (node (ref "U6") (pin "85") (pinfunction "IO_85") (pintype "bidirectional"))
    )
    (net (code "15") (name "/AI") (class "Default")
      (node (ref "R26") (pin "1") (pinfunction "1_1") (pintype "passive"))
      (node (ref "R27") (pin "2") (pinfunction "2_2") (pintype "passive"))
      (node (ref "U6") (pin "112") (pinfunction "IO_112") (pintype "bidirectional"))
    )
    (net (code "16") (name "/AI_LED") (class "Default")
      (node (ref "D8") (pin "2") (pinfunction "Anode_2") (pintype "passive"))
      (node (ref "U6") (pin "24") (pinfunction "IO_24") (pintype "bidirectional"))
    )
    (net (code "17") (name "/AO") (class "Default")
      (node (ref "R21") (pin "1") (pinfunction "1_1") (pintype "passive"))
      (node (ref "R22") (pin "2") (pinfunction "2_2") (pintype "passive"))
      (node (ref "U6") (pin "111") (pinfunction "IO_111") (pintype "bidirectional"))
    )
    (net (code "18") (name "/AO_LED") (class "Default")
      (node (ref "D9") (pin "2") (pinfunction "Anode_2") (pintype "passive"))
      (node (ref "U6") (pin "23") (pinfunction "IO_23") (pintype "bidirectional"))
    )
    (net (code "19") (name "/BI") (class "Default")
      (node (ref "R57") (pin "2") (pinfunction "2_2") (pintype "passive"))
      (node (ref "R58") (pin "2") (pinfunction "2_2") (pintype "passive"))
      (node (ref "U6") (pin "108") (pinfunction "IO_108") (pintype "bidirectional"))
    )
    (net (code "20") (name "/BI_LED") (class "Default")
      (node (ref "D12") (pin "2") (pinfunction "Anode_2") (pintype "passive"))
      (node (ref "U6") (pin "20") (pinfunction "IO/GCLK1_20") (pintype "bidirectional"))
    )
    (net (code "21") (name "/CE") (class "Default")
      (node (ref "R63") (pin "2") (pinfunction "2_2") (pintype "passive"))
      (node (ref "R64") (pin "2") (pinfunction "2_2") (pintype "passive"))
      (node (ref "U6") (pin "106") (pinfunction "IO_106") (pintype "bidirectional"))
    )
    (net (code "22") (name "/CE_LED") (class "Default")
      (node (ref "D14") (pin "2") (pinfunction "Anode_2") (pintype "passive"))
      (node (ref "U6") (pin "16") (pinfunction "IO_16") (pintype "bidirectional"))
    )
    (net (code "23") (name "/CF") (class "Default")
      (node (ref "U2") (pin "23") (pinfunction "A8_23") (pintype "passive"))
      (node (ref "U4") (pin "23") (pinfunction "A8_23") (pintype "passive"))
      (node (ref "U6") (pin "102") (pinfunction "IO_102") (pintype "bidirectional"))
    )
    (net (code "24") (name "/CLK") (class "Default")
      (node (ref "U6") (pin "91") (pinfunction "IO/GCLK3_91") (pintype "bidirectional"))
      (node (ref "Y1") (pin "3") (pinfunction "OUTPUT_3") (pintype "output"))
    )
    (net (code "25") (name "/CLR") (class "Default")
      (node (ref "C5") (pin "2") (pinfunction "2_2") (pintype "passive"))
      (node (ref "R67") (pin "1") (pinfunction "1_1") (pintype "passive"))
      (node (ref "U6") (pin "61") (pinfunction "IO/DEV_CLRn_61") (pintype "bidirectional"))
    )
    (net (code "26") (name "/CO") (class "Default")
      (node (ref "R59") (pin "1") (pinfunction "1_1") (pintype "passive"))
      (node (ref "R60") (pin "2") (pinfunction "2_2") (pintype "passive"))
      (node (ref "U6") (pin "105") (pinfunction "IO_105") (pintype "bidirectional"))
    )
    (net (code "27") (name "/CO_LED") (class "Default")
      (node (ref "D15") (pin "2") (pinfunction "Anode_2") (pintype "passive"))
      (node (ref "U6") (pin "15") (pinfunction "IO_15") (pintype "bidirectional"))
    )
    (net (code "28") (name "/DA_SW_0") (class "Default")
      (node (ref "R7") (pin "2") (pinfunction "2_2") (pintype "passive"))
      (node (ref "S2") (pin "1") (pinfunction "COM_1_1") (pintype "passive"))
      (node (ref "U6") (pin "84") (pinfunction "IO_84") (pintype "bidirectional"))
    )
    (net (code "29") (name "/DA_SW_1") (class "Default")
      (node (ref "R8") (pin "2") (pinfunction "2_2") (pintype "passive"))
      (node (ref "S2") (pin "2") (pinfunction "COM_2_2") (pintype "passive"))
      (node (ref "U6") (pin "81") (pinfunction "IO_81") (pintype "bidirectional"))
    )
    (net (code "30") (name "/DA_SW_2") (class "Default")
      (node (ref "R9") (pin "2") (pinfunction "2_2") (pintype "passive"))
      (node (ref "S2") (pin "3") (pinfunction "COM_3_3") (pintype "passive"))
      (node (ref "U6") (pin "80") (pinfunction "IO_80") (pintype "bidirectional"))
    )
    (net (code "31") (name "/DA_SW_3") (class "Default")
      (node (ref "R11") (pin "2") (pinfunction "2_2") (pintype "passive"))
      (node (ref "S2") (pin "4") (pinfunction "COM_4_4") (pintype "passive"))
      (node (ref "U6") (pin "79") (pinfunction "IO_79") (pintype "bidirectional"))
    )
    (net (code "32") (name "/DA_SW_4") (class "Default")
      (node (ref "R36") (pin "2") (pinfunction "2_2") (pintype "passive"))
      (node (ref "S3") (pin "1") (pinfunction "COM_1_1") (pintype "passive"))
      (node (ref "U6") (pin "78") (pinfunction "IO_78") (pintype "bidirectional"))
    )
    (net (code "33") (name "/DA_SW_5") (class "Default")
      (node (ref "R37") (pin "2") (pinfunction "2_2") (pintype "passive"))
      (node (ref "S3") (pin "2") (pinfunction "COM_2_2") (pintype "passive"))
      (node (ref "U6") (pin "77") (pinfunction "IO_77") (pintype "bidirectional"))
    )
    (net (code "34") (name "/DA_SW_6") (class "Default")
      (node (ref "R39") (pin "2") (pinfunction "2_2") (pintype "passive"))
      (node (ref "S3") (pin "3") (pinfunction "COM_3_3") (pintype "passive"))
      (node (ref "U6") (pin "76") (pinfunction "IO_76") (pintype "bidirectional"))
    )
    (net (code "35") (name "/DA_SW_7") (class "Default")
      (node (ref "R40") (pin "2") (pinfunction "2_2") (pintype "passive"))
      (node (ref "S3") (pin "4") (pinfunction "COM_4_4") (pintype "passive"))
      (node (ref "U6") (pin "75") (pinfunction "IO_75") (pintype "bidirectional"))
    )
    (net (code "36") (name "/EO") (class "Default")
      (node (ref "R47") (pin "2") (pinfunction "2_2") (pintype "passive"))
      (node (ref "R48") (pin "2") (pinfunction "2_2") (pintype "passive"))
      (node (ref "U6") (pin "110") (pinfunction "IO_110") (pintype "bidirectional"))
    )
    (net (code "37") (name "/EO_LED") (class "Default")
      (node (ref "D10") (pin "2") (pinfunction "Anode_2") (pintype "passive"))
      (node (ref "U6") (pin "22") (pinfunction "IO_22") (pintype "bidirectional"))
    )
    (net (code "38") (name "/FI") (class "Default")
      (node (ref "R51") (pin "1") (pinfunction "1_1") (pintype "passive"))
      (node (ref "R52") (pin "2") (pinfunction "2_2") (pintype "passive"))
      (node (ref "U6") (pin "103") (pinfunction "IO_103") (pintype "bidirectional"))
    )
    (net (code "39") (name "/FI_LED") (class "Default")
      (node (ref "D17") (pin "2") (pinfunction "Anode_2") (pintype "passive"))
      (node (ref "U6") (pin "13") (pinfunction "IO_13") (pintype "bidirectional"))
    )
    (net (code "40") (name "/G_TCK") (class "Default")
      (node (ref "J2") (pin "1") (pinfunction "1_1") (pintype "passive"))
      (node (ref "R70") (pin "2") (pinfunction "2_2") (pintype "passive"))
      (node (ref "U6") (pin "35") (pinfunction "TCK_35") (pintype "input"))
    )
    (net (code "41") (name "/G_TDI") (class "Default")
      (node (ref "J2") (pin "9") (pinfunction "9_9") (pintype "passive"))
      (node (ref "U6") (pin "34") (pinfunction "TDI_34") (pintype "input"))
    )
    (net (code "42") (name "/G_TDO") (class "Default")
      (node (ref "J2") (pin "3") (pinfunction "3_3") (pintype "passive"))
      (node (ref "R66") (pin "1") (pinfunction "1_1") (pintype "passive"))
      (node (ref "U6") (pin "36") (pinfunction "TDO_36") (pintype "output"))
    )
    (net (code "43") (name "/G_TMS") (class "Default")
      (node (ref "J2") (pin "5") (pinfunction "5_5") (pintype "passive"))
      (node (ref "R65") (pin "1") (pinfunction "1_1") (pintype "passive"))
      (node (ref "U6") (pin "33") (pinfunction "TMS_33") (pintype "input"))
    )
    (net (code "44") (name "/HLT") (class "Default")
      (node (ref "R17") (pin "2") (pinfunction "2_2") (pintype "passive"))
      (node (ref "R18") (pin "2") (pinfunction "2_2") (pintype "passive"))
      (node (ref "U6") (pin "120") (pinfunction "IO_120") (pintype "bidirectional"))
    )
    (net (code "45") (name "/HLT_LED") (class "Default")
      (node (ref "D2") (pin "2") (pinfunction "Anode_2") (pintype "passive"))
      (node (ref "U6") (pin "32") (pinfunction "IO_32") (pintype "bidirectional"))
    )
    (net (code "46") (name "/II") (class "Default")
      (node (ref "R30") (pin "1") (pinfunction "1_1") (pintype "passive"))
      (node (ref "R31") (pin "2") (pinfunction "2_2") (pintype "passive"))
      (node (ref "U6") (pin "113") (pinfunction "IO_113") (pintype "bidirectional"))
    )
    (net (code "47") (name "/II_LED") (class "Default")
      (node (ref "D7") (pin "2") (pinfunction "Anode_2") (pintype "passive"))
      (node (ref "U6") (pin "27") (pinfunction "IO_27") (pintype "bidirectional"))
    )
    (net (code "48") (name "/IO") (class "Default")
      (node (ref "R34") (pin "2") (pinfunction "2_2") (pintype "passive"))
      (node (ref "R35") (pin "2") (pinfunction "2_2") (pintype "passive"))
      (node (ref "U6") (pin "114") (pinfunction "IO_114") (pintype "bidirectional"))
    )
    (net (code "49") (name "/IO_60") (class "Default")
      (node (ref "R117") (pin "1") (pinfunction "1_1") (pintype "passive"))
      (node (ref "U6") (pin "60") (pinfunction "IO/DEV_OE_60") (pintype "bidirectional"))
    )
    (net (code "50") (name "/IO_73") (class "Default")
      (node (ref "J4") (pin "2") (pinfunction "2_2") (pintype "passive"))
      (node (ref "U6") (pin "73") (pinfunction "IO_73") (pintype "bidirectional"))
    )
    (net (code "51") (name "/IO_74") (class "Default")
      (node (ref "J4") (pin "3") (pinfunction "3_3") (pintype "passive"))
      (node (ref "U6") (pin "74") (pinfunction "IO_74") (pintype "bidirectional"))
    )
    (net (code "52") (name "/IO_89") (class "Default")
      (node (ref "J4") (pin "5") (pinfunction "5_5") (pintype "passive"))
      (node (ref "U6") (pin "89") (pinfunction "IO/GCLK2_89") (pintype "bidirectional"))
    )
    (net (code "53") (name "/IO_LED") (class "Default")
      (node (ref "D6") (pin "2") (pinfunction "Anode_2") (pintype "passive"))
      (node (ref "U6") (pin "28") (pinfunction "IO_28") (pintype "bidirectional"))
    )
    (net (code "54") (name "/Instcnt_0") (class "Default")
      (node (ref "U2") (pin "8") (pinfunction "A0_8") (pintype "passive"))
      (node (ref "U4") (pin "8") (pinfunction "A0_8") (pintype "passive"))
      (node (ref "U6") (pin "68") (pinfunction "IO_68") (pintype "bidirectional"))
    )
    (net (code "55") (name "/Instcnt_1") (class "Default")
      (node (ref "U2") (pin "7") (pinfunction "A1_7") (pintype "passive"))
      (node (ref "U4") (pin "7") (pinfunction "A1_7") (pintype "passive"))
      (node (ref "U6") (pin "67") (pinfunction "IO_67") (pintype "bidirectional"))
    )
    (net (code "56") (name "/Instcnt_2") (class "Default")
      (node (ref "U2") (pin "6") (pinfunction "A2_6") (pintype "passive"))
      (node (ref "U4") (pin "6") (pinfunction "A2_6") (pintype "passive"))
      (node (ref "U6") (pin "66") (pinfunction "IO_66") (pintype "bidirectional"))
    )
    (net (code "57") (name "/JMP") (class "Default")
      (node (ref "R55") (pin "1") (pinfunction "1_1") (pintype "passive"))
      (node (ref "R56") (pin "2") (pinfunction "2_2") (pintype "passive"))
      (node (ref "U6") (pin "104") (pinfunction "IO_104") (pintype "bidirectional"))
    )
    (net (code "58") (name "/JMP_LED") (class "Default")
      (node (ref "D16") (pin "2") (pinfunction "Anode_2") (pintype "passive"))
      (node (ref "U6") (pin "14") (pinfunction "IO_14") (pintype "bidirectional"))
    )
    (net (code "59") (name "/MI") (class "Default")
      (node (ref "R23") (pin "2") (pinfunction "2_2") (pintype "passive"))
      (node (ref "R24") (pin "2") (pinfunction "2_2") (pintype "passive"))
      (node (ref "U6") (pin "119") (pinfunction "IO_119") (pintype "bidirectional"))
    )
    (net (code "60") (name "/MI_LED") (class "Default")
      (node (ref "D3") (pin "2") (pinfunction "Anode_2") (pintype "passive"))
      (node (ref "U6") (pin "31") (pinfunction "IO_31") (pintype "bidirectional"))
    )
    (net (code "61") (name "/OI") (class "Default")
      (node (ref "R61") (pin "2") (pinfunction "2_2") (pintype "passive"))
      (node (ref "R62") (pin "2") (pinfunction "2_2") (pintype "passive"))
      (node (ref "U6") (pin "107") (pinfunction "IO_107") (pintype "bidirectional"))
    )
    (net (code "62") (name "/OI_LED") (class "Default")
      (node (ref "D13") (pin "2") (pinfunction "Anode_2") (pintype "passive"))
      (node (ref "U6") (pin "18") (pinfunction "IO/GCLK0_18") (pintype "bidirectional"))
    )
    (net (code "63") (name "/Opcode_0") (class "Default")
      (node (ref "U2") (pin "5") (pinfunction "A3_5") (pintype "passive"))
      (node (ref "U4") (pin "5") (pinfunction "A3_5") (pintype "passive"))
      (node (ref "U6") (pin "72") (pinfunction "IO_72") (pintype "bidirectional"))
    )
    (net (code "64") (name "/Opcode_1") (class "Default")
      (node (ref "U2") (pin "4") (pinfunction "A4_4") (pintype "passive"))
      (node (ref "U4") (pin "4") (pinfunction "A4_4") (pintype "passive"))
      (node (ref "U6") (pin "71") (pinfunction "IO_71") (pintype "bidirectional"))
    )
    (net (code "65") (name "/Opcode_2") (class "Default")
      (node (ref "U2") (pin "3") (pinfunction "A5_3") (pintype "passive"))
      (node (ref "U4") (pin "3") (pinfunction "A5_3") (pintype "passive"))
      (node (ref "U6") (pin "70") (pinfunction "IO_70") (pintype "bidirectional"))
    )
    (net (code "66") (name "/Opcode_3") (class "Default")
      (node (ref "U2") (pin "2") (pinfunction "A6_2") (pintype "passive"))
      (node (ref "U4") (pin "2") (pinfunction "A6_2") (pintype "passive"))
      (node (ref "U6") (pin "69") (pinfunction "IO_69") (pintype "bidirectional"))
    )
    (net (code "67") (name "/PROG_OR_RUN") (class "Default")
      (node (ref "R6") (pin "1") (pinfunction "1_1") (pintype "passive"))
      (node (ref "U6") (pin "95") (pinfunction "IO_95") (pintype "bidirectional"))
    )
    (net (code "68") (name "/PULSE") (class "Default")
      (node (ref "R102") (pin "2") (pinfunction "2_2") (pintype "passive"))
      (node (ref "SW5") (pin "1") (pintype "passive"))
      (node (ref "U6") (pin "97") (pinfunction "IO_97") (pintype "bidirectional"))
    )
    (net (code "69") (name "/PULSE_OR_CLK") (class "Default")
      (node (ref "R14") (pin "1") (pinfunction "1_1") (pintype "passive"))
      (node (ref "U6") (pin "94") (pinfunction "IO_94") (pintype "bidirectional"))
    )
    (net (code "70") (name "/RESET") (class "Default")
      (node (ref "R103") (pin "2") (pinfunction "2_2") (pintype "passive"))
      (node (ref "SW4") (pin "1") (pintype "passive"))
      (node (ref "U6") (pin "98") (pinfunction "IO_98") (pintype "bidirectional"))
    )
    (net (code "71") (name "/RI") (class "Default")
      (node (ref "R28") (pin "2") (pinfunction "2_2") (pintype "passive"))
      (node (ref "R29") (pin "2") (pinfunction "2_2") (pintype "passive"))
      (node (ref "U6") (pin "118") (pinfunction "IO_118") (pintype "bidirectional"))
    )
    (net (code "72") (name "/RI_LED") (class "Default")
      (node (ref "D4") (pin "2") (pinfunction "Anode_2") (pintype "passive"))
      (node (ref "U6") (pin "30") (pinfunction "IO_30") (pintype "bidirectional"))
    )
    (net (code "73") (name "/RO") (class "Default")
      (node (ref "R32") (pin "2") (pinfunction "2_2") (pintype "passive"))
      (node (ref "R33") (pin "2") (pinfunction "2_2") (pintype "passive"))
      (node (ref "U6") (pin "117") (pinfunction "IO_117") (pintype "bidirectional"))
    )
    (net (code "74") (name "/RO_LED") (class "Default")
      (node (ref "D5") (pin "2") (pinfunction "Anode_2") (pintype "passive"))
      (node (ref "U6") (pin "29") (pinfunction "IO_29") (pintype "bidirectional"))
    )
    (net (code "75") (name "/R_AD_0") (class "Default")
      (node (ref "U3") (pin "1") (pinfunction "A0_1") (pintype "passive"))
      (node (ref "U5") (pin "1") (pinfunction "A0_1") (pintype "passive"))
      (node (ref "U6") (pin "121") (pinfunction "IO_121") (pintype "bidirectional"))
    )
    (net (code "76") (name "/R_AD_1") (class "Default")
      (node (ref "U3") (pin "15") (pinfunction "A1_15") (pintype "passive"))
      (node (ref "U5") (pin "15") (pinfunction "A1_15") (pintype "passive"))
      (node (ref "U6") (pin "122") (pinfunction "IO_122") (pintype "bidirectional"))
    )
    (net (code "77") (name "/R_AD_2") (class "Default")
      (node (ref "U3") (pin "14") (pinfunction "A2_14") (pintype "passive"))
      (node (ref "U5") (pin "14") (pinfunction "A2_14") (pintype "passive"))
      (node (ref "U6") (pin "123") (pinfunction "IO_123") (pintype "bidirectional"))
    )
    (net (code "78") (name "/R_AD_3") (class "Default")
      (node (ref "U3") (pin "13") (pinfunction "A3_13") (pintype "passive"))
      (node (ref "U5") (pin "13") (pinfunction "A3_13") (pintype "passive"))
      (node (ref "U6") (pin "124") (pinfunction "IO_124") (pintype "bidirectional"))
    )
    (net (code "79") (name "/R_D_0") (class "Default")
      (node (ref "U3") (pin "4") (pinfunction "D0_4") (pintype "passive"))
      (node (ref "U6") (pin "125") (pinfunction "IO_125") (pintype "bidirectional"))
    )
    (net (code "80") (name "/R_D_1") (class "Default")
      (node (ref "U3") (pin "6") (pinfunction "D1_6") (pintype "passive"))
      (node (ref "U6") (pin "127") (pinfunction "IO_127") (pintype "bidirectional"))
    )
    (net (code "81") (name "/R_D_2") (class "Default")
      (node (ref "U3") (pin "10") (pinfunction "D2_10") (pintype "passive"))
      (node (ref "U6") (pin "129") (pinfunction "IO_129") (pintype "bidirectional"))
    )
    (net (code "82") (name "/R_D_3") (class "Default")
      (node (ref "U3") (pin "12") (pinfunction "D3_12") (pintype "passive"))
      (node (ref "U6") (pin "130") (pinfunction "IO_130") (pintype "bidirectional"))
    )
    (net (code "83") (name "/R_D_4") (class "Default")
      (node (ref "U5") (pin "4") (pinfunction "D0_4") (pintype "passive"))
      (node (ref "U6") (pin "131") (pinfunction "IO_131") (pintype "bidirectional"))
    )
    (net (code "84") (name "/R_D_5") (class "Default")
      (node (ref "U5") (pin "6") (pinfunction "D1_6") (pintype "passive"))
      (node (ref "U6") (pin "132") (pinfunction "IO_132") (pintype "bidirectional"))
    )
    (net (code "85") (name "/R_D_6") (class "Default")
      (node (ref "U5") (pin "10") (pinfunction "D2_10") (pintype "passive"))
      (node (ref "U6") (pin "133") (pinfunction "IO_133") (pintype "bidirectional"))
    )
    (net (code "86") (name "/R_D_7") (class "Default")
      (node (ref "U5") (pin "12") (pinfunction "D3_12") (pintype "passive"))
      (node (ref "U6") (pin "134") (pinfunction "IO_134") (pintype "bidirectional"))
    )
    (net (code "87") (name "/R_O_0") (class "Default")
      (node (ref "R10") (pin "1") (pinfunction "1_1") (pintype "passive"))
      (node (ref "R12") (pin "1") (pinfunction "1_1") (pintype "passive"))
      (node (ref "U6") (pin "137") (pinfunction "IO_137") (pintype "bidirectional"))
    )
    (net (code "88") (name "/R_O_1") (class "Default")
      (node (ref "R15") (pin "1") (pinfunction "1_1") (pintype "passive"))
      (node (ref "R19") (pin "1") (pinfunction "1_1") (pintype "passive"))
      (node (ref "U6") (pin "138") (pinfunction "IO_138") (pintype "bidirectional"))
    )
    (net (code "89") (name "/R_O_2") (class "Default")
      (node (ref "R20") (pin "2") (pinfunction "2_2") (pintype "passive"))
      (node (ref "R25") (pin "2") (pinfunction "2_2") (pintype "passive"))
      (node (ref "U6") (pin "139") (pinfunction "IO_139") (pintype "bidirectional"))
    )
    (net (code "90") (name "/R_O_3") (class "Default")
      (node (ref "R13") (pin "2") (pinfunction "2_2") (pintype "passive"))
      (node (ref "R16") (pin "2") (pinfunction "2_2") (pintype "passive"))
      (node (ref "U6") (pin "140") (pinfunction "IO_140") (pintype "bidirectional"))
    )
    (net (code "91") (name "/R_O_4") (class "Default")
      (node (ref "R41") (pin "1") (pinfunction "1_1") (pintype "passive"))
      (node (ref "R42") (pin "1") (pinfunction "1_1") (pintype "passive"))
      (node (ref "U6") (pin "141") (pinfunction "IO_141") (pintype "bidirectional"))
    )
    (net (code "92") (name "/R_O_5") (class "Default")
      (node (ref "R45") (pin "1") (pinfunction "1_1") (pintype "passive"))
      (node (ref "R46") (pin "1") (pinfunction "1_1") (pintype "passive"))
      (node (ref "U6") (pin "142") (pinfunction "IO_142") (pintype "bidirectional"))
    )
    (net (code "93") (name "/R_O_6") (class "Default")
      (node (ref "R49") (pin "2") (pinfunction "2_2") (pintype "passive"))
      (node (ref "R50") (pin "2") (pinfunction "2_2") (pintype "passive"))
      (node (ref "U6") (pin "143") (pinfunction "IO_143") (pintype "bidirectional"))
    )
    (net (code "94") (name "/R_O_7") (class "Default")
      (node (ref "R43") (pin "2") (pinfunction "2_2") (pintype "passive"))
      (node (ref "R44") (pin "2") (pinfunction "2_2") (pintype "passive"))
      (node (ref "U6") (pin "144") (pinfunction "IO_144") (pintype "bidirectional"))
    )
    (net (code "95") (name "/R_WE") (class "Default")
      (node (ref "U3") (pin "3") (pinfunction "~{WE}_3") (pintype "passive"))
      (node (ref "U5") (pin "3") (pinfunction "~{WE}_3") (pintype "passive"))
      (node (ref "U6") (pin "2") (pinfunction "IO_2") (pintype "bidirectional"))
    )
    (net (code "96") (name "/SU") (class "Default")
      (node (ref "R53") (pin "2") (pinfunction "2_2") (pintype "passive"))
      (node (ref "R54") (pin "2") (pinfunction "2_2") (pintype "passive"))
      (node (ref "U6") (pin "109") (pinfunction "IO_109") (pintype "bidirectional"))
    )
    (net (code "97") (name "/SU_LED") (class "Default")
      (node (ref "D11") (pin "2") (pinfunction "Anode_2") (pintype "passive"))
      (node (ref "U6") (pin "21") (pinfunction "IO_21") (pintype "bidirectional"))
    )
    (net (code "98") (name "/TWOS_OR_ONES") (class "Default")
      (node (ref "R38") (pin "1") (pinfunction "1_1") (pintype "passive"))
      (node (ref "U6") (pin "93") (pinfunction "IO_93") (pintype "bidirectional"))
    )
    (net (code "99") (name "/WE_BUT") (class "Default")
      (node (ref "R101") (pin "2") (pinfunction "2_2") (pintype "passive"))
      (node (ref "SW6") (pin "1") (pintype "passive"))
      (node (ref "U6") (pin "96") (pinfunction "IO_96") (pintype "bidirectional"))
    )
    (net (code "100") (name "/ZF") (class "Default")
      (node (ref "U2") (pin "22") (pinfunction "A9_22") (pintype "passive"))
      (node (ref "U4") (pin "22") (pinfunction "A9_22") (pintype "passive"))
      (node (ref "U6") (pin "101") (pinfunction "IO_101") (pintype "bidirectional"))
    )
    (net (code "101") (name "GND") (class "Default")
      (node (ref "C1") (pin "2") (pinfunction "2_2") (pintype "passive"))
      (node (ref "C10") (pin "1") (pinfunction "1_1") (pintype "passive"))
      (node (ref "C11") (pin "1") (pinfunction "1_1") (pintype "passive"))
      (node (ref "C12") (pin "1") (pinfunction "1_1") (pintype "passive"))
      (node (ref "C13") (pin "1") (pinfunction "1_1") (pintype "passive"))
      (node (ref "C2") (pin "2") (pinfunction "2_2") (pintype "passive"))
      (node (ref "C3") (pin "1") (pinfunction "1_1") (pintype "passive"))
      (node (ref "C4") (pin "1") (pinfunction "1_1") (pintype "passive"))
      (node (ref "C5") (pin "1") (pinfunction "1_1") (pintype "passive"))
      (node (ref "C6") (pin "1") (pinfunction "1_1") (pintype "passive"))
      (node (ref "C7") (pin "1") (pinfunction "1_1") (pintype "passive"))
      (node (ref "C8") (pin "1") (pinfunction "1_1") (pintype "passive"))
      (node (ref "C9") (pin "1") (pinfunction "1_1") (pintype "passive"))
      (node (ref "D1") (pin "1") (pinfunction "Cathode_1") (pintype "passive"))
      (node (ref "J1") (pin "2") (pinfunction "2_2") (pintype "passive"))
      (node (ref "J1") (pin "3") (pinfunction "3_3") (pintype "passive"))
      (node (ref "J2") (pin "10") (pinfunction "10_10") (pintype "passive"))
      (node (ref "J2") (pin "2") (pinfunction "2_2") (pintype "passive"))
      (node (ref "J3") (pin "2") (pinfunction "2_2") (pintype "passive"))
      (node (ref "J3") (pin "4") (pinfunction "4_4") (pintype "passive"))
      (node (ref "R10") (pin "2") (pinfunction "2_2") (pintype "passive"))
      (node (ref "R100") (pin "2") (pinfunction "2_2") (pintype "passive"))
      (node (ref "R101") (pin "1") (pinfunction "1_1") (pintype "passive"))
      (node (ref "R102") (pin "1") (pinfunction "1_1") (pintype "passive"))
      (node (ref "R103") (pin "1") (pinfunction "1_1") (pintype "passive"))
      (node (ref "R106") (pin "2") (pinfunction "2_2") (pintype "passive"))
      (node (ref "R109") (pin "2") (pinfunction "2_2") (pintype "passive"))
      (node (ref "R11") (pin "1") (pinfunction "1_1") (pintype "passive"))
      (node (ref "R112") (pin "2") (pinfunction "2_2") (pintype "passive"))
      (node (ref "R115") (pin "2") (pinfunction "2_2") (pintype "passive"))
      (node (ref "R116") (pin "2") (pinfunction "2_2") (pintype "passive"))
      (node (ref "R15") (pin "2") (pinfunction "2_2") (pintype "passive"))
      (node (ref "R16") (pin "1") (pinfunction "1_1") (pintype "passive"))
      (node (ref "R18") (pin "1") (pinfunction "1_1") (pintype "passive"))
      (node (ref "R2") (pin "1") (pinfunction "1_1") (pintype "passive"))
      (node (ref "R21") (pin "2") (pinfunction "2_2") (pintype "passive"))
      (node (ref "R24") (pin "1") (pinfunction "1_1") (pintype "passive"))
      (node (ref "R25") (pin "1") (pinfunction "1_1") (pintype "passive"))
      (node (ref "R26") (pin "2") (pinfunction "2_2") (pintype "passive"))
      (node (ref "R29") (pin "1") (pinfunction "1_1") (pintype "passive"))
      (node (ref "R3") (pin "1") (pinfunction "1_1") (pintype "passive"))
      (node (ref "R30") (pin "2") (pinfunction "2_2") (pintype "passive"))
      (node (ref "R33") (pin "1") (pinfunction "1_1") (pintype "passive"))
      (node (ref "R35") (pin "1") (pinfunction "1_1") (pintype "passive"))
      (node (ref "R36") (pin "1") (pinfunction "1_1") (pintype "passive"))
      (node (ref "R37") (pin "1") (pinfunction "1_1") (pintype "passive"))
      (node (ref "R39") (pin "1") (pinfunction "1_1") (pintype "passive"))
      (node (ref "R4") (pin "1") (pinfunction "1_1") (pintype "passive"))
      (node (ref "R40") (pin "1") (pinfunction "1_1") (pintype "passive"))
      (node (ref "R41") (pin "2") (pinfunction "2_2") (pintype "passive"))
      (node (ref "R44") (pin "1") (pinfunction "1_1") (pintype "passive"))
      (node (ref "R45") (pin "2") (pinfunction "2_2") (pintype "passive"))
      (node (ref "R48") (pin "1") (pinfunction "1_1") (pintype "passive"))
      (node (ref "R5") (pin "1") (pinfunction "1_1") (pintype "passive"))
      (node (ref "R50") (pin "1") (pinfunction "1_1") (pintype "passive"))
      (node (ref "R51") (pin "2") (pinfunction "2_2") (pintype "passive"))
      (node (ref "R54") (pin "1") (pinfunction "1_1") (pintype "passive"))
      (node (ref "R55") (pin "2") (pinfunction "2_2") (pintype "passive"))
      (node (ref "R58") (pin "1") (pinfunction "1_1") (pintype "passive"))
      (node (ref "R59") (pin "2") (pinfunction "2_2") (pintype "passive"))
      (node (ref "R62") (pin "1") (pinfunction "1_1") (pintype "passive"))
      (node (ref "R64") (pin "1") (pinfunction "1_1") (pintype "passive"))
      (node (ref "R68") (pin "2") (pinfunction "2_2") (pintype "passive"))
      (node (ref "R69") (pin "2") (pinfunction "2_2") (pintype "passive"))
      (node (ref "R7") (pin "1") (pinfunction "1_1") (pintype "passive"))
      (node (ref "R70") (pin "1") (pinfunction "1_1") (pintype "passive"))
      (node (ref "R71") (pin "2") (pinfunction "2_2") (pintype "passive"))
      (node (ref "R72") (pin "2") (pinfunction "2_2") (pintype "passive"))
      (node (ref "R73") (pin "2") (pinfunction "2_2") (pintype "passive"))
      (node (ref "R74") (pin "2") (pinfunction "2_2") (pintype "passive"))
      (node (ref "R75") (pin "2") (pinfunction "2_2") (pintype "passive"))
      (node (ref "R76") (pin "2") (pinfunction "2_2") (pintype "passive"))
      (node (ref "R77") (pin "2") (pinfunction "2_2") (pintype "passive"))
      (node (ref "R78") (pin "2") (pinfunction "2_2") (pintype "passive"))
      (node (ref "R79") (pin "2") (pinfunction "2_2") (pintype "passive"))
      (node (ref "R8") (pin "1") (pinfunction "1_1") (pintype "passive"))
      (node (ref "R80") (pin "2") (pinfunction "2_2") (pintype "passive"))
      (node (ref "R82") (pin "2") (pinfunction "2_2") (pintype "passive"))
      (node (ref "R85") (pin "2") (pinfunction "2_2") (pintype "passive"))
      (node (ref "R88") (pin "2") (pinfunction "2_2") (pintype "passive"))
      (node (ref "R9") (pin "1") (pinfunction "1_1") (pintype "passive"))
      (node (ref "R91") (pin "2") (pinfunction "2_2") (pintype "passive"))
      (node (ref "R94") (pin "2") (pinfunction "2_2") (pintype "passive"))
      (node (ref "R97") (pin "2") (pinfunction "2_2") (pintype "passive"))
      (node (ref "SW1") (pin "3") (pinfunction "3_3") (pintype "passive"))
      (node (ref "SW2") (pin "3") (pinfunction "3_3") (pintype "passive"))
      (node (ref "SW3") (pin "3") (pinfunction "3_3") (pintype "passive"))
      (node (ref "U1") (pin "1") (pinfunction "GND_1") (pintype "input"))
      (node (ref "U2") (pin "1") (pinfunction "A7_1") (pintype "passive"))
      (node (ref "U2") (pin "12") (pinfunction "VSS_12") (pintype "passive"))
      (node (ref "U2") (pin "18") (pinfunction "~CE_18") (pintype "passive"))
      (node (ref "U2") (pin "19") (pinfunction "A10_19") (pintype "passive"))
      (node (ref "U2") (pin "20") (pinfunction "~OE_20") (pintype "passive"))
      (node (ref "U3") (pin "2") (pinfunction "~{CS}_2") (pintype "passive"))
      (node (ref "U3") (pin "8") (pinfunction "GND_8") (pintype "passive"))
      (node (ref "U4") (pin "12") (pinfunction "VSS_12") (pintype "passive"))
      (node (ref "U4") (pin "18") (pinfunction "~CE_18") (pintype "passive"))
      (node (ref "U4") (pin "19") (pinfunction "A10_19") (pintype "passive"))
      (node (ref "U4") (pin "20") (pinfunction "~OE_20") (pintype "passive"))
      (node (ref "U5") (pin "2") (pinfunction "~{CS}_2") (pintype "passive"))
      (node (ref "U5") (pin "8") (pinfunction "GND_8") (pintype "passive"))
      (node (ref "U6") (pin "10") (pinfunction "GNDIO_10") (pintype "power_in"))
      (node (ref "U6") (pin "115") (pinfunction "GNDIO_115") (pintype "power_in"))
      (node (ref "U6") (pin "128") (pinfunction "GNDINT_128") (pintype "power_in"))
      (node (ref "U6") (pin "135") (pinfunction "GNDIO_135") (pintype "power_in"))
      (node (ref "U6") (pin "17") (pinfunction "GNDINT_17") (pintype "power_in"))
      (node (ref "U6") (pin "26") (pinfunction "GNDIO_26") (pintype "power_in"))
      (node (ref "U6") (pin "47") (pinfunction "GNDIO_47") (pintype "power_in"))
      (node (ref "U6") (pin "54") (pinfunction "GNDINT_54") (pintype "power_in"))
      (node (ref "U6") (pin "65") (pinfunction "GNDIO_65") (pintype "power_in"))
      (node (ref "U6") (pin "83") (pinfunction "GNDIO_83") (pintype "power_in"))
      (node (ref "U6") (pin "92") (pinfunction "GNDINT_92") (pintype "power_in"))
      (node (ref "U6") (pin "99") (pinfunction "GNDIO_99") (pintype "power_in"))
      (node (ref "Y1") (pin "2") (pinfunction "GND_2") (pintype "power_in"))
    )
    (net (code "102") (name "Net-(D1-Anode)") (class "Default")
      (node (ref "D1") (pin "2") (pinfunction "Anode_2") (pintype "passive"))
      (node (ref "R1") (pin "1") (pinfunction "1_1") (pintype "passive"))
    )
    (net (code "103") (name "Net-(D2-Cathode)") (class "Default")
      (node (ref "D2") (pin "1") (pinfunction "Cathode_1") (pintype "passive"))
      (node (ref "R68") (pin "1") (pinfunction "1_1") (pintype "passive"))
    )
    (net (code "104") (name "Net-(D3-Cathode)") (class "Default")
      (node (ref "D3") (pin "1") (pinfunction "Cathode_1") (pintype "passive"))
      (node (ref "R69") (pin "1") (pinfunction "1_1") (pintype "passive"))
    )
    (net (code "105") (name "Net-(D4-Cathode)") (class "Default")
      (node (ref "D4") (pin "1") (pinfunction "Cathode_1") (pintype "passive"))
      (node (ref "R71") (pin "1") (pinfunction "1_1") (pintype "passive"))
    )
    (net (code "106") (name "Net-(D5-Cathode)") (class "Default")
      (node (ref "D5") (pin "1") (pinfunction "Cathode_1") (pintype "passive"))
      (node (ref "R72") (pin "1") (pinfunction "1_1") (pintype "passive"))
    )
    (net (code "107") (name "Net-(D6-Cathode)") (class "Default")
      (node (ref "D6") (pin "1") (pinfunction "Cathode_1") (pintype "passive"))
      (node (ref "R73") (pin "1") (pinfunction "1_1") (pintype "passive"))
    )
    (net (code "108") (name "Net-(D7-Cathode)") (class "Default")
      (node (ref "D7") (pin "1") (pinfunction "Cathode_1") (pintype "passive"))
      (node (ref "R74") (pin "1") (pinfunction "1_1") (pintype "passive"))
    )
    (net (code "109") (name "Net-(D8-Cathode)") (class "Default")
      (node (ref "D8") (pin "1") (pinfunction "Cathode_1") (pintype "passive"))
      (node (ref "R75") (pin "1") (pinfunction "1_1") (pintype "passive"))
    )
    (net (code "110") (name "Net-(D9-Cathode)") (class "Default")
      (node (ref "D9") (pin "1") (pinfunction "Cathode_1") (pintype "passive"))
      (node (ref "R76") (pin "1") (pinfunction "1_1") (pintype "passive"))
    )
    (net (code "111") (name "Net-(D10-Cathode)") (class "Default")
      (node (ref "D10") (pin "1") (pinfunction "Cathode_1") (pintype "passive"))
      (node (ref "R77") (pin "1") (pinfunction "1_1") (pintype "passive"))
    )
    (net (code "112") (name "Net-(D11-Cathode)") (class "Default")
      (node (ref "D11") (pin "1") (pinfunction "Cathode_1") (pintype "passive"))
      (node (ref "R78") (pin "1") (pinfunction "1_1") (pintype "passive"))
    )
    (net (code "113") (name "Net-(D12-Cathode)") (class "Default")
      (node (ref "D12") (pin "1") (pinfunction "Cathode_1") (pintype "passive"))
      (node (ref "R79") (pin "1") (pinfunction "1_1") (pintype "passive"))
    )
    (net (code "114") (name "Net-(D13-Cathode)") (class "Default")
      (node (ref "D13") (pin "1") (pinfunction "Cathode_1") (pintype "passive"))
      (node (ref "R80") (pin "1") (pinfunction "1_1") (pintype "passive"))
    )
    (net (code "115") (name "Net-(D14-Cathode)") (class "Default")
      (node (ref "D14") (pin "1") (pinfunction "Cathode_1") (pintype "passive"))
      (node (ref "R82") (pin "1") (pinfunction "1_1") (pintype "passive"))
    )
    (net (code "116") (name "Net-(D15-Cathode)") (class "Default")
      (node (ref "D15") (pin "1") (pinfunction "Cathode_1") (pintype "passive"))
      (node (ref "R85") (pin "1") (pinfunction "1_1") (pintype "passive"))
    )
    (net (code "117") (name "Net-(D16-Cathode)") (class "Default")
      (node (ref "D16") (pin "1") (pinfunction "Cathode_1") (pintype "passive"))
      (node (ref "R88") (pin "1") (pinfunction "1_1") (pintype "passive"))
    )
    (net (code "118") (name "Net-(D17-Cathode)") (class "Default")
      (node (ref "D17") (pin "1") (pinfunction "Cathode_1") (pintype "passive"))
      (node (ref "R91") (pin "1") (pinfunction "1_1") (pintype "passive"))
    )
    (net (code "119") (name "Net-(D18-Cathode)") (class "Default")
      (node (ref "D18") (pin "1") (pinfunction "Cathode_1") (pintype "passive"))
      (node (ref "R94") (pin "1") (pinfunction "1_1") (pintype "passive"))
    )
    (net (code "120") (name "Net-(D19-Cathode)") (class "Default")
      (node (ref "D19") (pin "1") (pinfunction "Cathode_1") (pintype "passive"))
      (node (ref "R97") (pin "1") (pinfunction "1_1") (pintype "passive"))
    )
    (net (code "121") (name "Net-(D20-Cathode)") (class "Default")
      (node (ref "D20") (pin "1") (pinfunction "Cathode_1") (pintype "passive"))
      (node (ref "R100") (pin "1") (pinfunction "1_1") (pintype "passive"))
    )
    (net (code "122") (name "Net-(D21-Cathode)") (class "Default")
      (node (ref "D21") (pin "1") (pinfunction "Cathode_1") (pintype "passive"))
      (node (ref "R106") (pin "1") (pinfunction "1_1") (pintype "passive"))
    )
    (net (code "123") (name "Net-(D22-Cathode)") (class "Default")
      (node (ref "D22") (pin "1") (pinfunction "Cathode_1") (pintype "passive"))
      (node (ref "R109") (pin "1") (pinfunction "1_1") (pintype "passive"))
    )
    (net (code "124") (name "Net-(D23-Cathode)") (class "Default")
      (node (ref "D23") (pin "1") (pinfunction "Cathode_1") (pintype "passive"))
      (node (ref "R112") (pin "1") (pinfunction "1_1") (pintype "passive"))
    )
    (net (code "125") (name "Net-(D24-Cathode)") (class "Default")
      (node (ref "D24") (pin "1") (pinfunction "Cathode_1") (pintype "passive"))
      (node (ref "R115") (pin "1") (pinfunction "1_1") (pintype "passive"))
    )
    (net (code "126") (name "Net-(D25-Cathode)") (class "Default")
      (node (ref "D25") (pin "1") (pinfunction "Cathode_1") (pintype "passive"))
      (node (ref "R116") (pin "1") (pinfunction "1_1") (pintype "passive"))
    )
    (net (code "127") (name "Net-(R6-Pad2)") (class "Default")
      (node (ref "R6") (pin "2") (pinfunction "2_2") (pintype "passive"))
      (node (ref "SW1") (pin "2") (pinfunction "2_2") (pintype "passive"))
    )
    (net (code "128") (name "Net-(R14-Pad2)") (class "Default")
      (node (ref "R14") (pin "2") (pinfunction "2_2") (pintype "passive"))
      (node (ref "SW2") (pin "2") (pinfunction "2_2") (pintype "passive"))
    )
    (net (code "129") (name "Net-(R38-Pad2)") (class "Default")
      (node (ref "R38") (pin "2") (pinfunction "2_2") (pintype "passive"))
      (node (ref "SW3") (pin "2") (pinfunction "2_2") (pintype "passive"))
    )
    (net (code "130") (name "Net-(R81-Pad1)") (class "Default")
      (node (ref "R81") (pin "1") (pinfunction "1_1") (pintype "passive"))
      (node (ref "U6") (pin "63") (pinfunction "IO_63") (pintype "bidirectional"))
    )
    (net (code "131") (name "Net-(R83-Pad1)") (class "Default")
      (node (ref "R83") (pin "1") (pinfunction "1_1") (pintype "passive"))
      (node (ref "U6") (pin "62") (pinfunction "IO_62") (pintype "bidirectional"))
    )
    (net (code "132") (name "Net-(R84-Pad1)") (class "Default")
      (node (ref "R84") (pin "1") (pinfunction "1_1") (pintype "passive"))
      (node (ref "U6") (pin "59") (pinfunction "IO_59") (pintype "bidirectional"))
    )
    (net (code "133") (name "Net-(R86-Pad1)") (class "Default")
      (node (ref "R86") (pin "1") (pinfunction "1_1") (pintype "passive"))
      (node (ref "U6") (pin "58") (pinfunction "IO_58") (pintype "bidirectional"))
    )
    (net (code "134") (name "Net-(R87-Pad1)") (class "Default")
      (node (ref "R87") (pin "1") (pinfunction "1_1") (pintype "passive"))
      (node (ref "U6") (pin "57") (pinfunction "IO_57") (pintype "bidirectional"))
    )
    (net (code "135") (name "Net-(R89-Pad1)") (class "Default")
      (node (ref "R89") (pin "1") (pinfunction "1_1") (pintype "passive"))
      (node (ref "U6") (pin "55") (pinfunction "IO_55") (pintype "bidirectional"))
    )
    (net (code "136") (name "Net-(R90-Pad1)") (class "Default")
      (node (ref "R90") (pin "1") (pinfunction "1_1") (pintype "passive"))
      (node (ref "U6") (pin "53") (pinfunction "IO_53") (pintype "bidirectional"))
    )
    (net (code "137") (name "Net-(R92-Pad1)") (class "Default")
      (node (ref "R92") (pin "1") (pinfunction "1_1") (pintype "passive"))
      (node (ref "U6") (pin "52") (pinfunction "IO_52") (pintype "bidirectional"))
    )
    (net (code "138") (name "Net-(R93-Pad1)") (class "Default")
      (node (ref "R93") (pin "1") (pinfunction "1_1") (pintype "passive"))
      (node (ref "U6") (pin "51") (pinfunction "IO_51") (pintype "bidirectional"))
    )
    (net (code "139") (name "Net-(R95-Pad1)") (class "Default")
      (node (ref "R95") (pin "1") (pinfunction "1_1") (pintype "passive"))
      (node (ref "U6") (pin "50") (pinfunction "IO_50") (pintype "bidirectional"))
    )
    (net (code "140") (name "Net-(R96-Pad1)") (class "Default")
      (node (ref "R96") (pin "1") (pinfunction "1_1") (pintype "passive"))
      (node (ref "U6") (pin "49") (pinfunction "IO_49") (pintype "bidirectional"))
    )
    (net (code "141") (name "Net-(R98-Pad1)") (class "Default")
      (node (ref "R98") (pin "1") (pinfunction "1_1") (pintype "passive"))
      (node (ref "U6") (pin "48") (pinfunction "IO_48") (pintype "bidirectional"))
    )
    (net (code "142") (name "Net-(R99-Pad1)") (class "Default")
      (node (ref "R99") (pin "1") (pinfunction "1_1") (pintype "passive"))
      (node (ref "U6") (pin "45") (pinfunction "IO_45") (pintype "bidirectional"))
    )
    (net (code "143") (name "Net-(R104-Pad1)") (class "Default")
      (node (ref "R104") (pin "1") (pinfunction "1_1") (pintype "passive"))
      (node (ref "U6") (pin "44") (pinfunction "IO_44") (pintype "bidirectional"))
    )
    (net (code "144") (name "Net-(R105-Pad1)") (class "Default")
      (node (ref "R105") (pin "1") (pinfunction "1_1") (pintype "passive"))
      (node (ref "U6") (pin "43") (pinfunction "IO_43") (pintype "bidirectional"))
    )
    (net (code "145") (name "Net-(R107-Pad1)") (class "Default")
      (node (ref "R107") (pin "1") (pinfunction "1_1") (pintype "passive"))
      (node (ref "U6") (pin "42") (pinfunction "IO_42") (pintype "bidirectional"))
    )
    (net (code "146") (name "Net-(R108-Pad1)") (class "Default")
      (node (ref "R108") (pin "1") (pinfunction "1_1") (pintype "passive"))
      (node (ref "U6") (pin "41") (pinfunction "IO_41") (pintype "bidirectional"))
    )
    (net (code "147") (name "Net-(R110-Pad1)") (class "Default")
      (node (ref "R110") (pin "1") (pinfunction "1_1") (pintype "passive"))
      (node (ref "U6") (pin "40") (pinfunction "IO_40") (pintype "bidirectional"))
    )
    (net (code "148") (name "Net-(R111-Pad1)") (class "Default")
      (node (ref "R111") (pin "1") (pinfunction "1_1") (pintype "passive"))
      (node (ref "U6") (pin "39") (pinfunction "IO_39") (pintype "bidirectional"))
    )
    (net (code "149") (name "Net-(R113-Pad1)") (class "Default")
      (node (ref "R113") (pin "1") (pinfunction "1_1") (pintype "passive"))
      (node (ref "U6") (pin "38") (pinfunction "IO_38") (pintype "bidirectional"))
    )
    (net (code "150") (name "Net-(R114-Pad1)") (class "Default")
      (node (ref "R114") (pin "1") (pinfunction "1_1") (pintype "passive"))
      (node (ref "U6") (pin "37") (pinfunction "IO_37") (pintype "bidirectional"))
    )
    (net (code "151") (name "Net-(U2-I{slash}O0)") (class "Default")
      (node (ref "R22") (pin "1") (pinfunction "1_1") (pintype "passive"))
      (node (ref "U2") (pin "9") (pinfunction "I/O0_9") (pintype "passive"))
    )
    (net (code "152") (name "Net-(U2-I{slash}O1)") (class "Default")
      (node (ref "R27") (pin "1") (pinfunction "1_1") (pintype "passive"))
      (node (ref "U2") (pin "10") (pinfunction "I/O1_10") (pintype "passive"))
    )
    (net (code "153") (name "Net-(U2-I{slash}O2)") (class "Default")
      (node (ref "R31") (pin "1") (pinfunction "1_1") (pintype "passive"))
      (node (ref "U2") (pin "11") (pinfunction "I/O2_11") (pintype "passive"))
    )
    (net (code "154") (name "Net-(U2-I{slash}O3)") (class "Default")
      (node (ref "R34") (pin "1") (pinfunction "1_1") (pintype "passive"))
      (node (ref "U2") (pin "13") (pinfunction "I/O3_13") (pintype "passive"))
    )
    (net (code "155") (name "Net-(U2-I{slash}O4)") (class "Default")
      (node (ref "R32") (pin "1") (pinfunction "1_1") (pintype "passive"))
      (node (ref "U2") (pin "14") (pinfunction "I/O4_14") (pintype "passive"))
    )
    (net (code "156") (name "Net-(U2-I{slash}O5)") (class "Default")
      (node (ref "R28") (pin "1") (pinfunction "1_1") (pintype "passive"))
      (node (ref "U2") (pin "15") (pinfunction "I/O5_15") (pintype "passive"))
    )
    (net (code "157") (name "Net-(U2-I{slash}O6)") (class "Default")
      (node (ref "R23") (pin "1") (pinfunction "1_1") (pintype "passive"))
      (node (ref "U2") (pin "16") (pinfunction "I/O6_16") (pintype "passive"))
    )
    (net (code "158") (name "Net-(U2-I{slash}O7)") (class "Default")
      (node (ref "R17") (pin "1") (pinfunction "1_1") (pintype "passive"))
      (node (ref "U2") (pin "17") (pinfunction "I/O7_17") (pintype "passive"))
    )
    (net (code "159") (name "Net-(U3-~{O0})") (class "Default")
      (node (ref "R12") (pin "2") (pinfunction "2_2") (pintype "passive"))
      (node (ref "U3") (pin "5") (pinfunction "~{O0}_5") (pintype "passive"))
    )
    (net (code "160") (name "Net-(U3-~{O1})") (class "Default")
      (node (ref "R19") (pin "2") (pinfunction "2_2") (pintype "passive"))
      (node (ref "U3") (pin "7") (pinfunction "~{O1}_7") (pintype "passive"))
    )
    (net (code "161") (name "Net-(U3-~{O2})") (class "Default")
      (node (ref "R20") (pin "1") (pinfunction "1_1") (pintype "passive"))
      (node (ref "U3") (pin "9") (pinfunction "~{O2}_9") (pintype "passive"))
    )
    (net (code "162") (name "Net-(U3-~{O3})") (class "Default")
      (node (ref "R13") (pin "1") (pinfunction "1_1") (pintype "passive"))
      (node (ref "U3") (pin "11") (pinfunction "~{O3}_11") (pintype "passive"))
    )
    (net (code "163") (name "Net-(U4-I{slash}O0)") (class "Default")
      (node (ref "R52") (pin "1") (pinfunction "1_1") (pintype "passive"))
      (node (ref "U4") (pin "9") (pinfunction "I/O0_9") (pintype "passive"))
    )
    (net (code "164") (name "Net-(U4-I{slash}O1)") (class "Default")
      (node (ref "R56") (pin "1") (pinfunction "1_1") (pintype "passive"))
      (node (ref "U4") (pin "10") (pinfunction "I/O1_10") (pintype "passive"))
    )
    (net (code "165") (name "Net-(U4-I{slash}O2)") (class "Default")
      (node (ref "R60") (pin "1") (pinfunction "1_1") (pintype "passive"))
      (node (ref "U4") (pin "11") (pinfunction "I/O2_11") (pintype "passive"))
    )
    (net (code "166") (name "Net-(U4-I{slash}O3)") (class "Default")
      (node (ref "R63") (pin "1") (pinfunction "1_1") (pintype "passive"))
      (node (ref "U4") (pin "13") (pinfunction "I/O3_13") (pintype "passive"))
    )
    (net (code "167") (name "Net-(U4-I{slash}O4)") (class "Default")
      (node (ref "R61") (pin "1") (pinfunction "1_1") (pintype "passive"))
      (node (ref "U4") (pin "14") (pinfunction "I/O4_14") (pintype "passive"))
    )
    (net (code "168") (name "Net-(U4-I{slash}O5)") (class "Default")
      (node (ref "R57") (pin "1") (pinfunction "1_1") (pintype "passive"))
      (node (ref "U4") (pin "15") (pinfunction "I/O5_15") (pintype "passive"))
    )
    (net (code "169") (name "Net-(U4-I{slash}O6)") (class "Default")
      (node (ref "R53") (pin "1") (pinfunction "1_1") (pintype "passive"))
      (node (ref "U4") (pin "16") (pinfunction "I/O6_16") (pintype "passive"))
    )
    (net (code "170") (name "Net-(U4-I{slash}O7)") (class "Default")
      (node (ref "R47") (pin "1") (pinfunction "1_1") (pintype "passive"))
      (node (ref "U4") (pin "17") (pinfunction "I/O7_17") (pintype "passive"))
    )
    (net (code "171") (name "Net-(U5-~{O0})") (class "Default")
      (node (ref "R42") (pin "2") (pinfunction "2_2") (pintype "passive"))
      (node (ref "U5") (pin "5") (pinfunction "~{O0}_5") (pintype "passive"))
    )
    (net (code "172") (name "Net-(U5-~{O1})") (class "Default")
      (node (ref "R46") (pin "2") (pinfunction "2_2") (pintype "passive"))
      (node (ref "U5") (pin "7") (pinfunction "~{O1}_7") (pintype "passive"))
    )
    (net (code "173") (name "Net-(U5-~{O2})") (class "Default")
      (node (ref "R49") (pin "1") (pinfunction "1_1") (pintype "passive"))
      (node (ref "U5") (pin "9") (pinfunction "~{O2}_9") (pintype "passive"))
    )
    (net (code "174") (name "Net-(U5-~{O3})") (class "Default")
      (node (ref "R43") (pin "1") (pinfunction "1_1") (pintype "passive"))
      (node (ref "U5") (pin "11") (pinfunction "~{O3}_11") (pintype "passive"))
    )
    (net (code "175") (name "Net-(U7-A)") (class "Default")
      (node (ref "R81") (pin "2") (pinfunction "2_2") (pintype "passive"))
      (node (ref "U7") (pin "7") (pinfunction "A_7") (pintype "passive"))
    )
    (net (code "176") (name "Net-(U7-B)") (class "Default")
      (node (ref "R83") (pin "2") (pinfunction "2_2") (pintype "passive"))
      (node (ref "U7") (pin "6") (pinfunction "B_6") (pintype "passive"))
    )
    (net (code "177") (name "Net-(U7-C)") (class "Default")
      (node (ref "R84") (pin "2") (pinfunction "2_2") (pintype "passive"))
      (node (ref "U7") (pin "4") (pinfunction "C_4") (pintype "passive"))
    )
    (net (code "178") (name "Net-(U7-D)") (class "Default")
      (node (ref "R86") (pin "2") (pinfunction "2_2") (pintype "passive"))
      (node (ref "U7") (pin "2") (pinfunction "D_2") (pintype "passive"))
    )
    (net (code "179") (name "Net-(U7-E)") (class "Default")
      (node (ref "R87") (pin "2") (pinfunction "2_2") (pintype "passive"))
      (node (ref "U7") (pin "1") (pinfunction "E_1") (pintype "passive"))
    )
    (net (code "180") (name "Net-(U7-F)") (class "Default")
      (node (ref "R89") (pin "2") (pinfunction "2_2") (pintype "passive"))
      (node (ref "U7") (pin "9") (pinfunction "F_9") (pintype "passive"))
    )
    (net (code "181") (name "Net-(U7-G)") (class "Default")
      (node (ref "R90") (pin "2") (pinfunction "2_2") (pintype "passive"))
      (node (ref "U7") (pin "10") (pinfunction "G_10") (pintype "passive"))
    )
    (net (code "182") (name "Net-(U8-A)") (class "Default")
      (node (ref "R92") (pin "2") (pinfunction "2_2") (pintype "passive"))
      (node (ref "U8") (pin "7") (pinfunction "A_7") (pintype "passive"))
    )
    (net (code "183") (name "Net-(U8-B)") (class "Default")
      (node (ref "R93") (pin "2") (pinfunction "2_2") (pintype "passive"))
      (node (ref "U8") (pin "6") (pinfunction "B_6") (pintype "passive"))
    )
    (net (code "184") (name "Net-(U8-C)") (class "Default")
      (node (ref "R95") (pin "2") (pinfunction "2_2") (pintype "passive"))
      (node (ref "U8") (pin "4") (pinfunction "C_4") (pintype "passive"))
    )
    (net (code "185") (name "Net-(U8-D)") (class "Default")
      (node (ref "R96") (pin "2") (pinfunction "2_2") (pintype "passive"))
      (node (ref "U8") (pin "2") (pinfunction "D_2") (pintype "passive"))
    )
    (net (code "186") (name "Net-(U8-E)") (class "Default")
      (node (ref "R98") (pin "2") (pinfunction "2_2") (pintype "passive"))
      (node (ref "U8") (pin "1") (pinfunction "E_1") (pintype "passive"))
    )
    (net (code "187") (name "Net-(U8-F)") (class "Default")
      (node (ref "R99") (pin "2") (pinfunction "2_2") (pintype "passive"))
      (node (ref "U8") (pin "9") (pinfunction "F_9") (pintype "passive"))
    )
    (net (code "188") (name "Net-(U8-G)") (class "Default")
      (node (ref "R104") (pin "2") (pinfunction "2_2") (pintype "passive"))
      (node (ref "U8") (pin "10") (pinfunction "G_10") (pintype "passive"))
    )
    (net (code "189") (name "Net-(U9-A)") (class "Default")
      (node (ref "R105") (pin "2") (pinfunction "2_2") (pintype "passive"))
      (node (ref "U9") (pin "7") (pinfunction "A_7") (pintype "passive"))
    )
    (net (code "190") (name "Net-(U9-B)") (class "Default")
      (node (ref "R107") (pin "2") (pinfunction "2_2") (pintype "passive"))
      (node (ref "U9") (pin "6") (pinfunction "B_6") (pintype "passive"))
    )
    (net (code "191") (name "Net-(U9-C)") (class "Default")
      (node (ref "R108") (pin "2") (pinfunction "2_2") (pintype "passive"))
      (node (ref "U9") (pin "4") (pinfunction "C_4") (pintype "passive"))
    )
    (net (code "192") (name "Net-(U9-D)") (class "Default")
      (node (ref "R110") (pin "2") (pinfunction "2_2") (pintype "passive"))
      (node (ref "U9") (pin "2") (pinfunction "D_2") (pintype "passive"))
    )
    (net (code "193") (name "Net-(U9-E)") (class "Default")
      (node (ref "R111") (pin "2") (pinfunction "2_2") (pintype "passive"))
      (node (ref "U9") (pin "1") (pinfunction "E_1") (pintype "passive"))
    )
    (net (code "194") (name "Net-(U9-F)") (class "Default")
      (node (ref "R113") (pin "2") (pinfunction "2_2") (pintype "passive"))
      (node (ref "U9") (pin "9") (pinfunction "F_9") (pintype "passive"))
    )
    (net (code "195") (name "Net-(U9-G)") (class "Default")
      (node (ref "R114") (pin "2") (pinfunction "2_2") (pintype "passive"))
      (node (ref "U9") (pin "10") (pinfunction "G_10") (pintype "passive"))
    )
    (net (code "196") (name "Net-(U10-G)") (class "Default")
      (node (ref "R117") (pin "2") (pinfunction "2_2") (pintype "passive"))
      (node (ref "U10") (pin "10") (pinfunction "G_10") (pintype "passive"))
    )
    (net (code "197") (name "unconnected-(J2-Pad6)") (class "Default")
      (node (ref "J2") (pin "6") (pinfunction "6_6") (pintype "passive+no_connect"))
    )
    (net (code "198") (name "unconnected-(J2-Pad7)") (class "Default")
      (node (ref "J2") (pin "7") (pinfunction "7_7") (pintype "passive+no_connect"))
    )
    (net (code "199") (name "unconnected-(J2-Pad8)") (class "Default")
      (node (ref "J2") (pin "8") (pinfunction "8_8") (pintype "passive+no_connect"))
    )
    (net (code "200") (name "unconnected-(J4-Pad1)") (class "Default")
      (node (ref "J4") (pin "1") (pinfunction "1_1") (pintype "passive+no_connect"))
    )
    (net (code "201") (name "unconnected-(J4-Pad4)") (class "Default")
      (node (ref "J4") (pin "4") (pinfunction "4_4") (pintype "passive+no_connect"))
    )
    (net (code "202") (name "unconnected-(J4-Pad6)") (class "Default")
      (node (ref "J4") (pin "6") (pinfunction "6_6") (pintype "passive+no_connect"))
    )
    (net (code "203") (name "unconnected-(MH1-Pad1)") (class "Default")
      (node (ref "MH1") (pin "1") (pinfunction "1_1") (pintype "passive"))
    )
    (net (code "204") (name "unconnected-(MH2-Pad1)") (class "Default")
      (node (ref "MH2") (pin "1") (pinfunction "1_1") (pintype "passive"))
    )
    (net (code "205") (name "unconnected-(MH3-Pad1)") (class "Default")
      (node (ref "MH3") (pin "1") (pinfunction "1_1") (pintype "passive"))
    )
    (net (code "206") (name "unconnected-(MH4-Pad1)") (class "Default")
      (node (ref "MH4") (pin "1") (pinfunction "1_1") (pintype "passive"))
    )
    (net (code "207") (name "unconnected-(SW4-Pad2)") (class "Default")
      (node (ref "SW4") (pin "2") (pintype "passive+no_connect"))
    )
    (net (code "208") (name "unconnected-(SW5-Pad2)") (class "Default")
      (node (ref "SW5") (pin "2") (pintype "passive+no_connect"))
    )
    (net (code "209") (name "unconnected-(SW6-Pad2)") (class "Default")
      (node (ref "SW6") (pin "2") (pintype "passive+no_connect"))
    )
    (net (code "210") (name "unconnected-(U6A-IO-Pad1)") (class "Default")
      (node (ref "U6") (pin "1") (pinfunction "IO_1") (pintype "bidirectional"))
    )
    (net (code "211") (name "unconnected-(U10-A-Pad7)") (class "Default")
      (node (ref "U10") (pin "7") (pinfunction "A_7") (pintype "passive"))
    )
    (net (code "212") (name "unconnected-(U10-B-Pad6)") (class "Default")
      (node (ref "U10") (pin "6") (pinfunction "B_6") (pintype "passive"))
    )
    (net (code "213") (name "unconnected-(U10-C-Pad4)") (class "Default")
      (node (ref "U10") (pin "4") (pinfunction "C_4") (pintype "passive"))
    )
    (net (code "214") (name "unconnected-(U10-D-Pad2)") (class "Default")
      (node (ref "U10") (pin "2") (pinfunction "D_2") (pintype "passive"))
    )
    (net (code "215") (name "unconnected-(U10-E-Pad1)") (class "Default")
      (node (ref "U10") (pin "1") (pinfunction "E_1") (pintype "passive"))
    )
    (net (code "216") (name "unconnected-(U10-F-Pad9)") (class "Default")
      (node (ref "U10") (pin "9") (pinfunction "F_9") (pintype "passive"))
    )
    (net (code "217") (name "unconnected-(Y1-VCONT-Pad1)") (class "Default")
      (node (ref "Y1") (pin "1") (pinfunction "VCONT_1") (pintype "input+no_connect"))
    )
  )
)
